# hh2019_proto_rev1_0_0.net
KiCad netlist of a schematic drawn in EAGLE
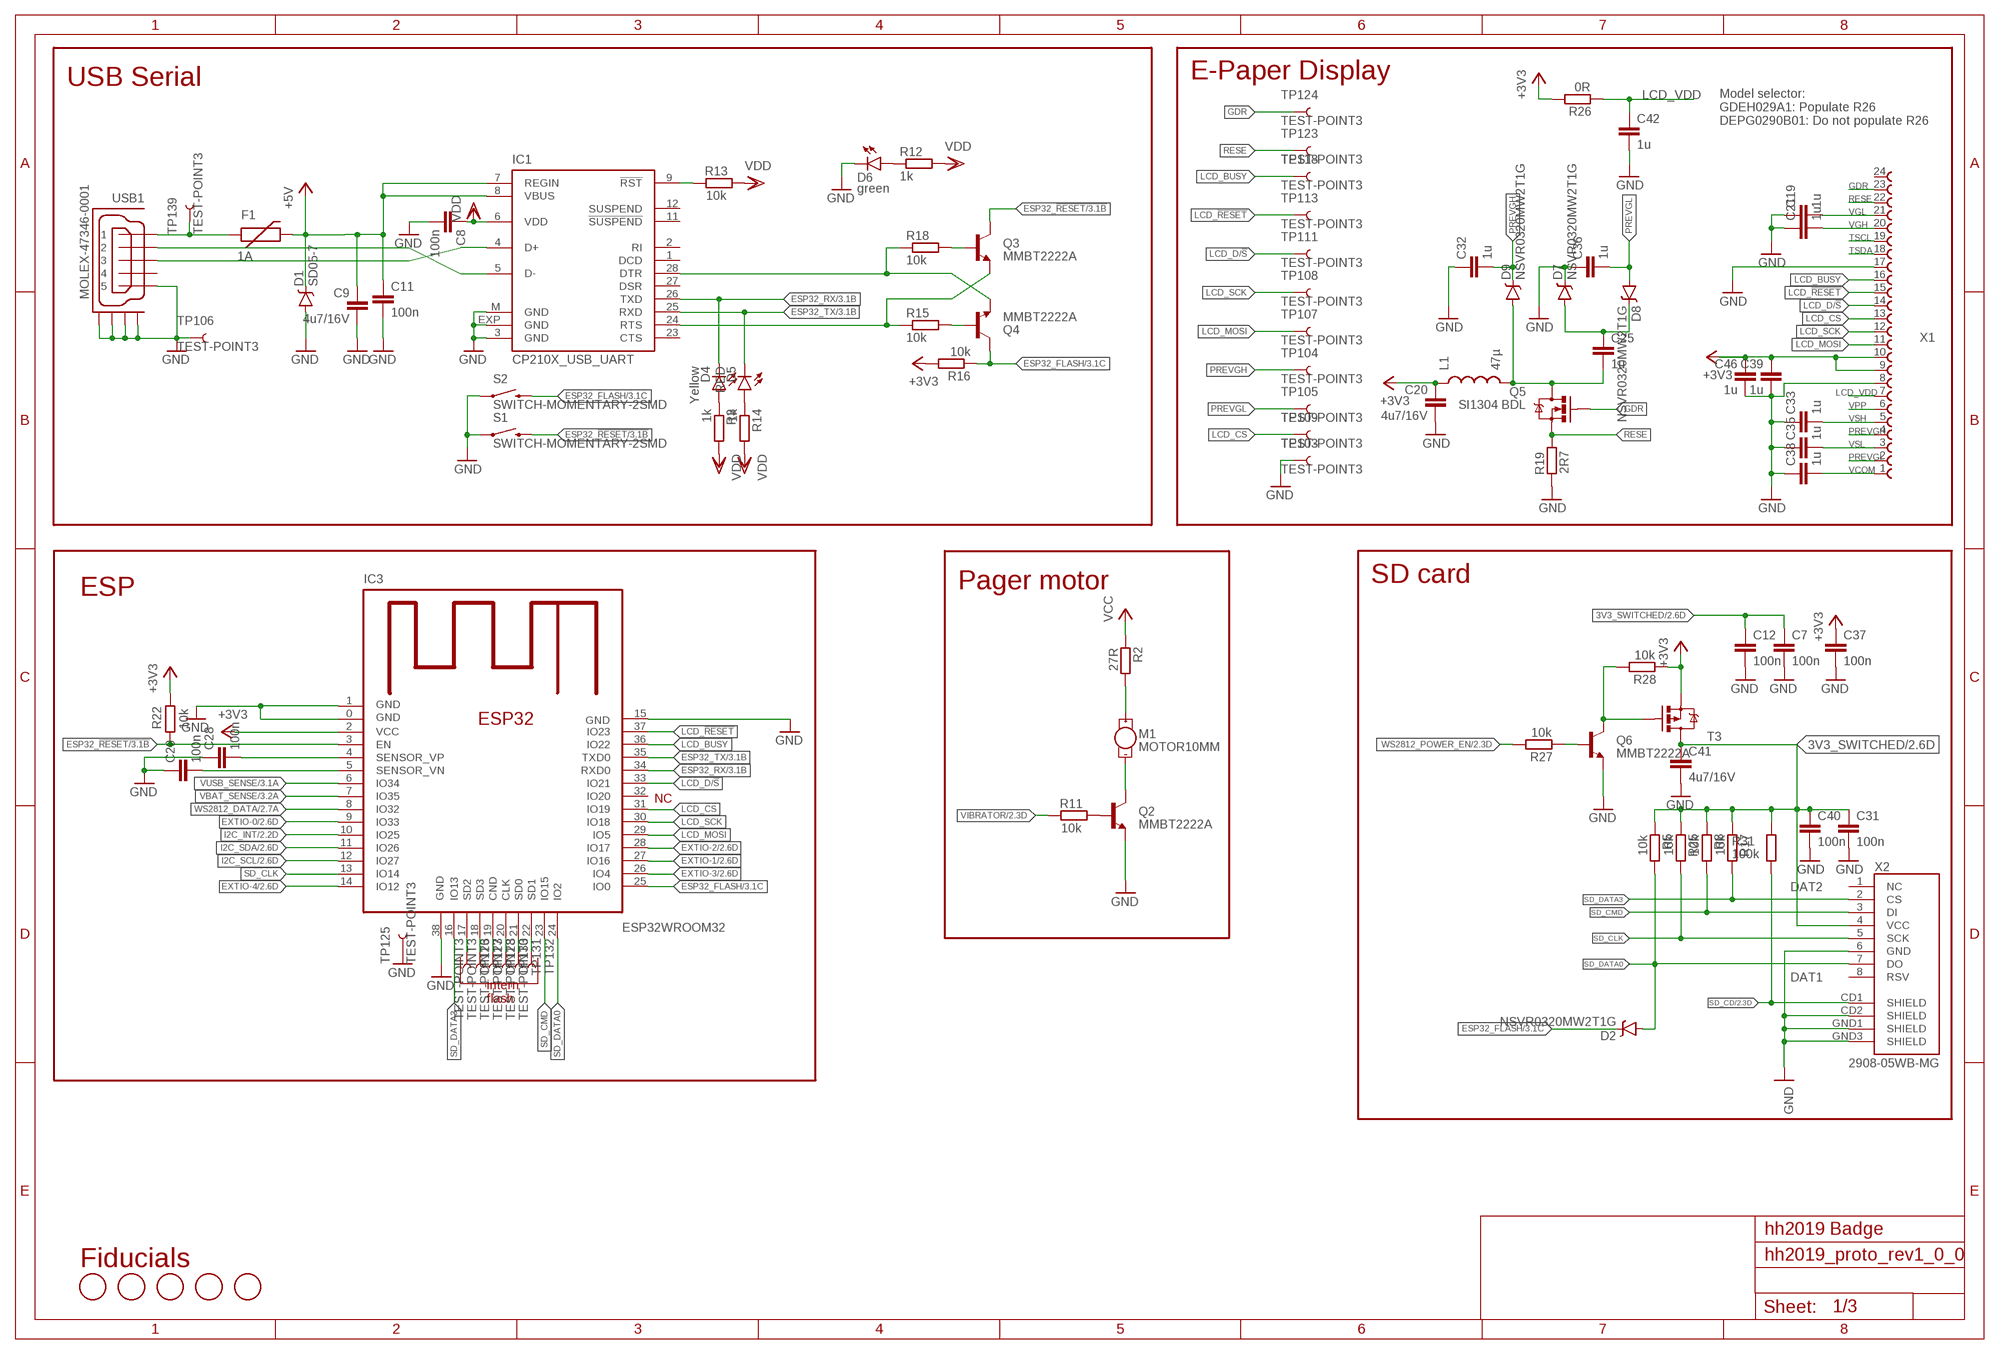
[diagram p0: schematic, sheet 1]
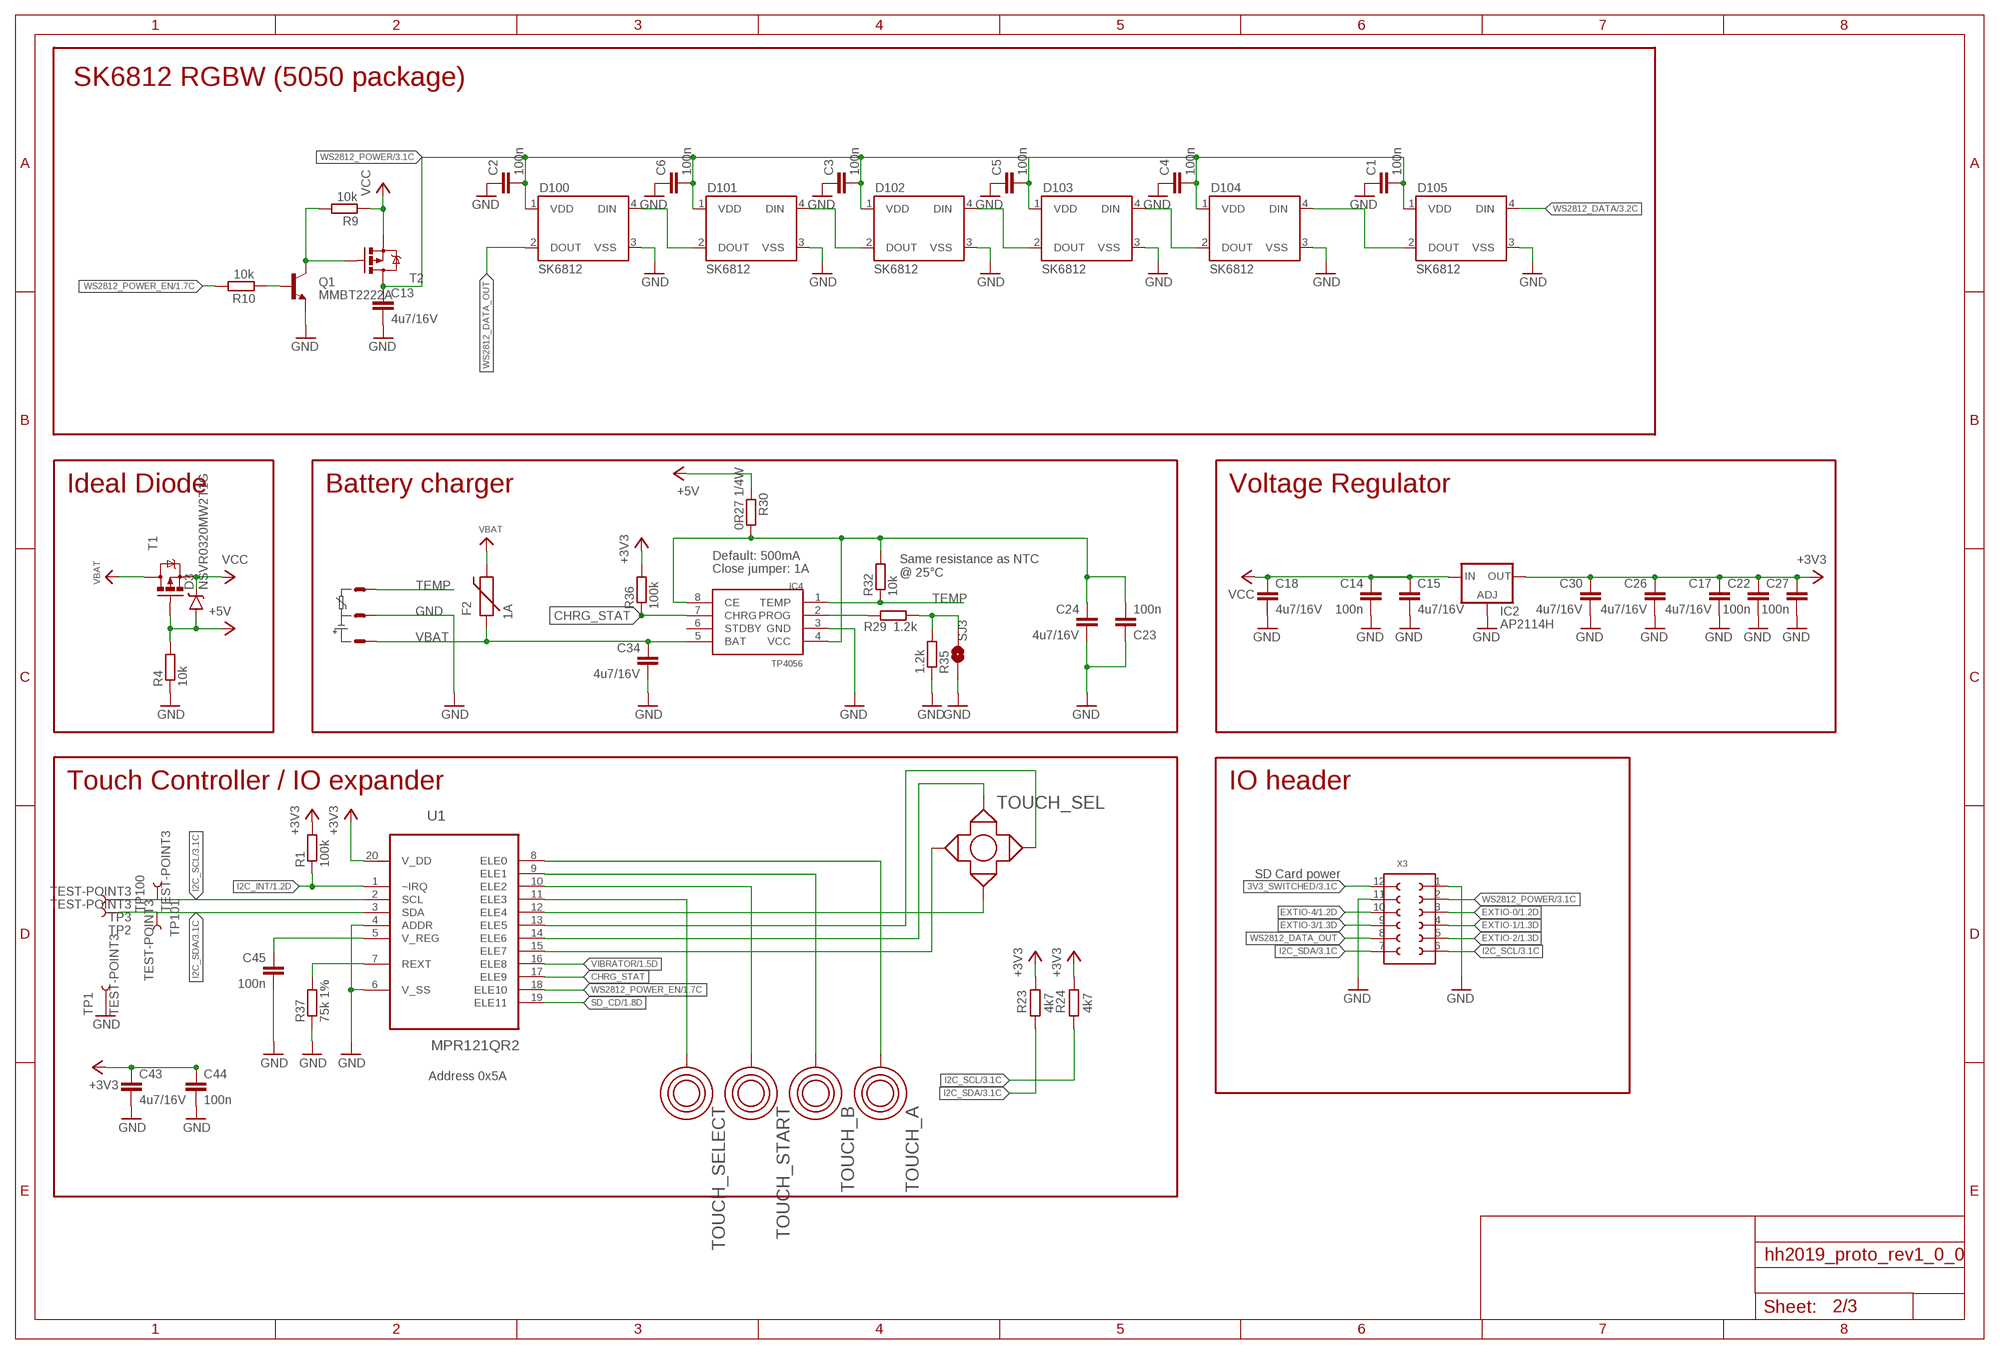
[diagram p1: schematic, sheet 2]
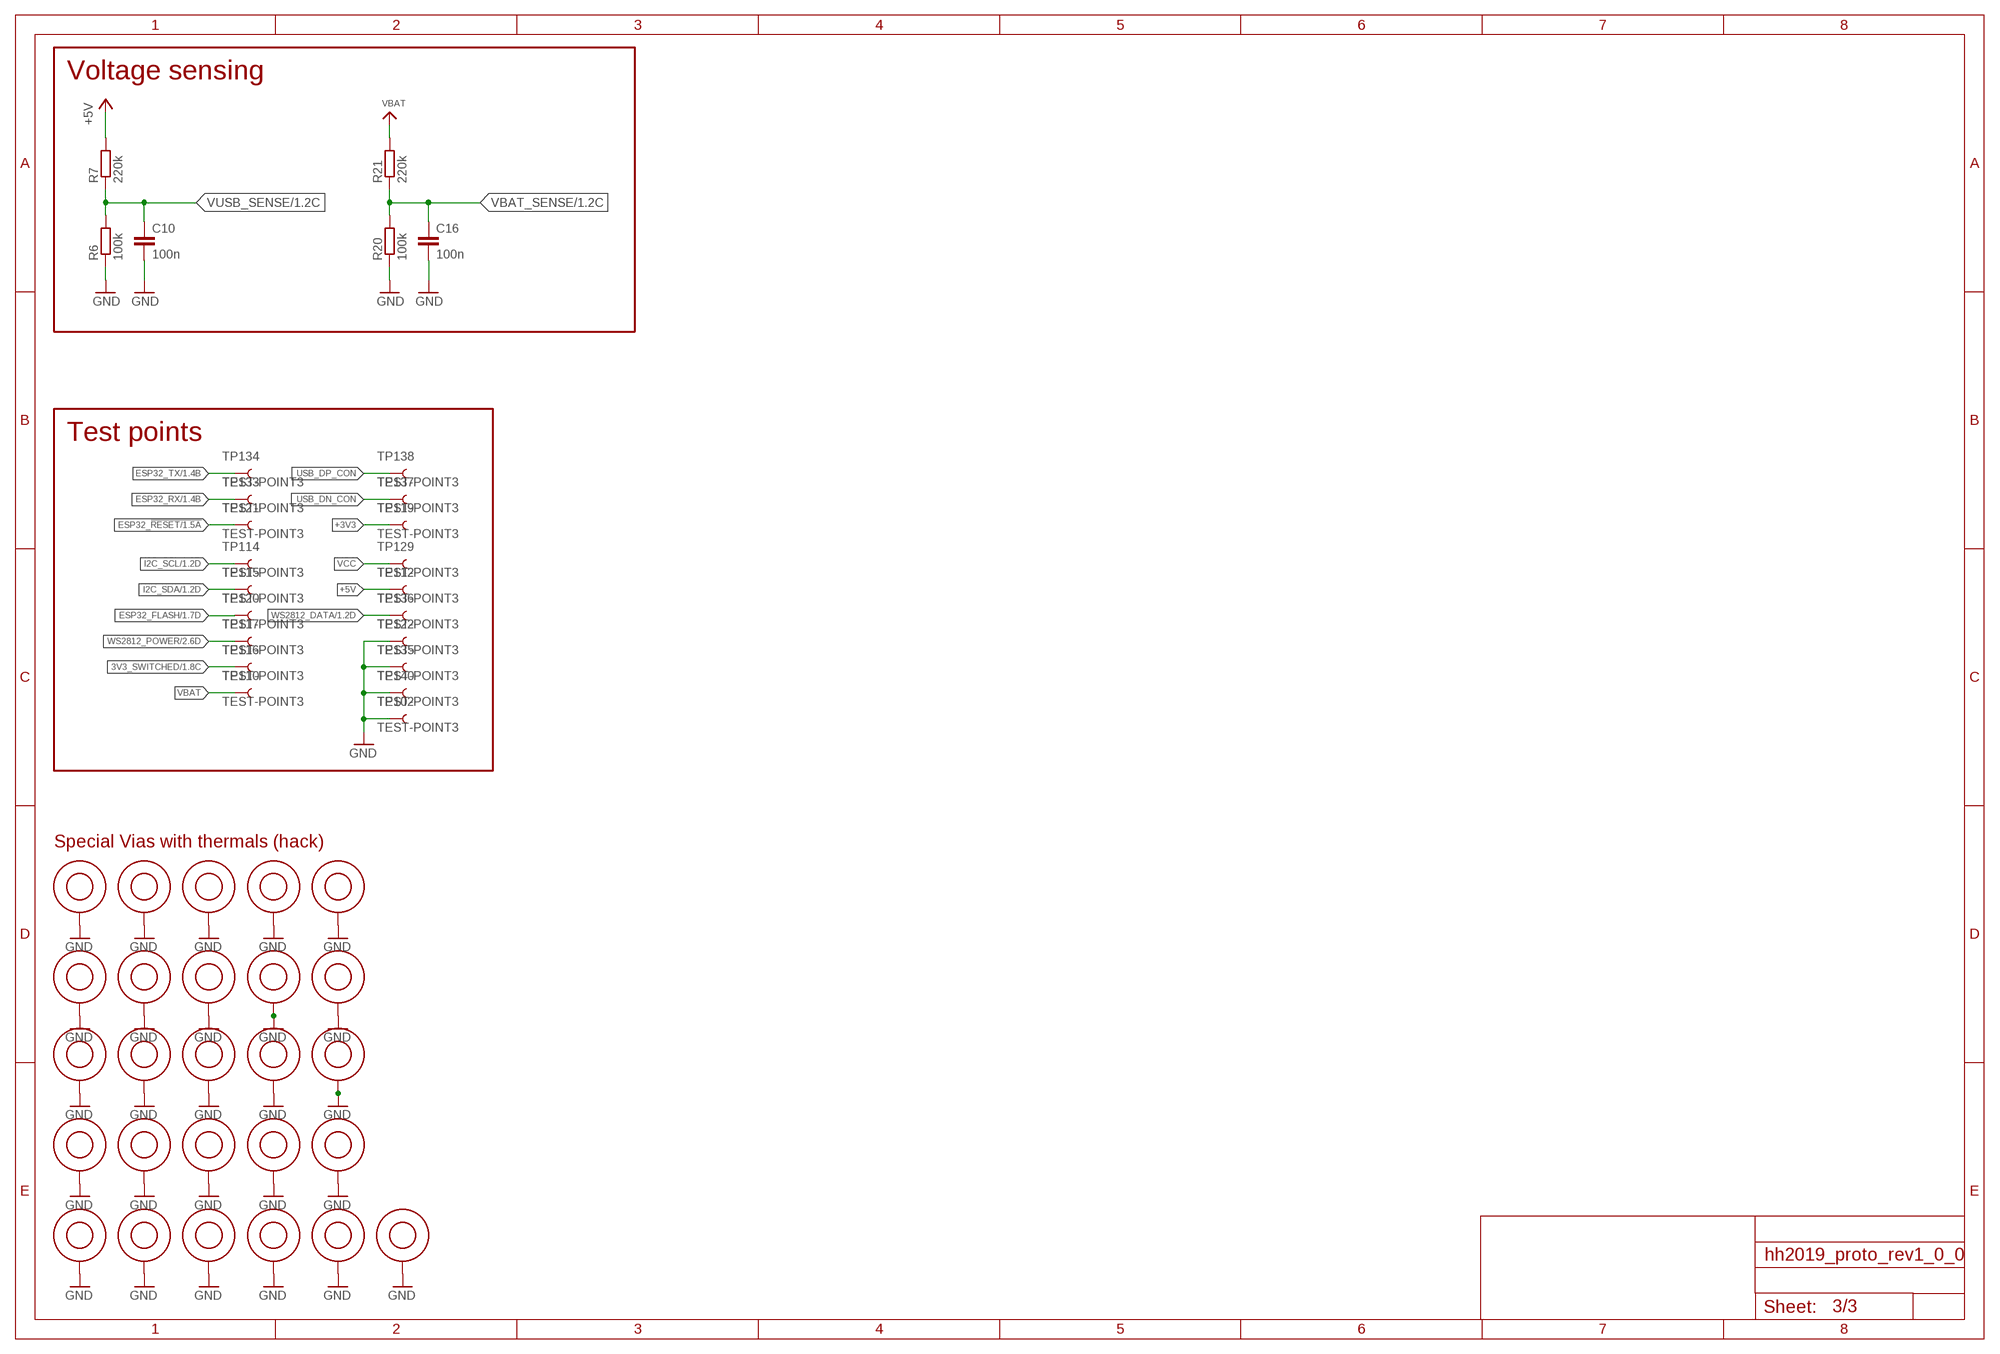
[diagram p2: schematic, sheet 3]

(export (version "E")
  (design (tool "Eeschema 10.0.6"))
  (components
    (comp (ref "C7")
      (value "100n")
      (footprint "eagle-import:C0603-DASHES")
      (fields (field (name "PARTNO") "GRM188R71H104KA93D"))
      (libsource (lib "eagle-import") (part "C0603-DASHES"))
    )
    (comp (ref "C8")
      (value "100n")
      (footprint "eagle-import:C0603-DASHES")
      (fields (field (name "PARTNO") "GRM188R71H104KA93D"))
      (libsource (lib "eagle-import") (part "C0603-DASHES"))
    )
    (comp (ref "C9")
      (value "4u7/16V")
      (footprint "eagle-import:C0805")
      (fields (field (name "PARTNO") "GRM21BR61C475KA88K"))
      (libsource (lib "eagle-import") (part "C-EUC0805"))
    )
    (comp (ref "C11")
      (value "100n")
      (footprint "eagle-import:C0603-DASHES")
      (fields (field (name "PARTNO") "GRM188R71H104KA93D"))
      (libsource (lib "eagle-import") (part "C0603-DASHES"))
    )
    (comp (ref "C12")
      (value "100n")
      (footprint "eagle-import:C0603-DASHES")
      (fields (field (name "PARTNO") "GRM188R71H104KA93D"))
      (libsource (lib "eagle-import") (part "C0603-DASHES"))
    )
    (comp (ref "C19")
      (value "1u")
      (footprint "eagle-import:C0603-DASHES")
      (fields (field (name "PARTNO") "GRM188R61E105KA12D"))
      (libsource (lib "eagle-import") (part "C0603-DASHES"))
    )
    (comp (ref "C20")
      (value "4u7/16V")
      (footprint "eagle-import:C0805")
      (fields (field (name "PARTNO") "GRM21BR61C475KA88K"))
      (libsource (lib "eagle-import") (part "C-EUC0805"))
    )
    (comp (ref "C21")
      (value "1u")
      (footprint "eagle-import:C0603-DASHES")
      (fields (field (name "PARTNO") "GRM188R61E105KA12D"))
      (libsource (lib "eagle-import") (part "C0603-DASHES"))
    )
    (comp (ref "C25")
      (value "1u")
      (footprint "eagle-import:C0603-DASHES")
      (fields (field (name "PARTNO") "GRM188R61E105KA12D"))
      (libsource (lib "eagle-import") (part "C0603-DASHES"))
    )
    (comp (ref "C28")
      (value "100n")
      (footprint "eagle-import:C0603-DASHES")
      (fields (field (name "PARTNO") "GRM188R71H104KA93D"))
      (libsource (lib "eagle-import") (part "C0603-DASHES"))
    )
    (comp (ref "C29")
      (value "100n")
      (footprint "eagle-import:C0603-DASHES")
      (fields (field (name "PARTNO") "GRM188R71H104KA93D"))
      (libsource (lib "eagle-import") (part "C0603-DASHES"))
    )
    (comp (ref "C31")
      (value "100n")
      (footprint "eagle-import:C0603-DASHES")
      (fields (field (name "PARTNO") "GRM188R71H104KA93D"))
      (libsource (lib "eagle-import") (part "C0603-DASHES"))
    )
    (comp (ref "C32")
      (value "1u")
      (footprint "eagle-import:C0603-DASHES")
      (fields (field (name "PARTNO") "GRM188R61E105KA12D"))
      (libsource (lib "eagle-import") (part "C0603-DASHES"))
    )
    (comp (ref "C33")
      (value "1u")
      (footprint "eagle-import:C0603-DASHES")
      (fields (field (name "PARTNO") "GRM188R61E105KA12D"))
      (libsource (lib "eagle-import") (part "C0603-DASHES"))
    )
    (comp (ref "C35")
      (value "1u")
      (footprint "eagle-import:C0603-DASHES")
      (fields (field (name "PARTNO") "GRM188R61E105KA12D"))
      (libsource (lib "eagle-import") (part "C0603-DASHES"))
    )
    (comp (ref "C36")
      (value "1u")
      (footprint "eagle-import:C0603-DASHES")
      (fields (field (name "PARTNO") "GRM188R61E105KA12D"))
      (libsource (lib "eagle-import") (part "C0603-DASHES"))
    )
    (comp (ref "C37")
      (value "100n")
      (footprint "eagle-import:C0603-DASHES")
      (fields (field (name "PARTNO") "GRM188R71H104KA93D"))
      (libsource (lib "eagle-import") (part "C0603-DASHES"))
    )
    (comp (ref "C38")
      (value "1u")
      (footprint "eagle-import:C0603-DASHES")
      (fields (field (name "PARTNO") "GRM188R61E105KA12D"))
      (libsource (lib "eagle-import") (part "C0603-DASHES"))
    )
    (comp (ref "C39")
      (value "1u")
      (footprint "eagle-import:C0603-DASHES")
      (fields (field (name "PARTNO") "GRM188R61E105KA12D"))
      (libsource (lib "eagle-import") (part "C0603-DASHES"))
    )
    (comp (ref "C40")
      (value "100n")
      (footprint "eagle-import:C0603-DASHES")
      (fields (field (name "PARTNO") "GRM188R71H104KA93D"))
      (libsource (lib "eagle-import") (part "C0603-DASHES"))
    )
    (comp (ref "C41")
      (value "4u7/16V")
      (footprint "eagle-import:C0805")
      (fields (field (name "PARTNO") "GRM21BR61C475KA88K"))
      (libsource (lib "eagle-import") (part "C-EUC0805"))
    )
    (comp (ref "C42")
      (value "1u")
      (footprint "eagle-import:C0603-DASHES")
      (fields (field (name "PARTNO") "GRM188R61E105KA12D"))
      (libsource (lib "eagle-import") (part "C0603-DASHES"))
    )
    (comp (ref "C46")
      (value "1u")
      (footprint "eagle-import:C0603-DASHES")
      (fields (field (name "PARTNO") "GRM188R61E105KA12D"))
      (libsource (lib "eagle-import") (part "C0603-DASHES"))
    )
    (comp (ref "D1")
      (value "SD05-7")
      (footprint "eagle-import:SOD-323")
      (libsource (lib "eagle-import") (part "DIODE-SCHOTTKY-PMEG4005EJ"))
    )
    (comp (ref "D2")
      (value "NSVR0320MW2T1G")
      (footprint "eagle-import:SOD-323")
      (fields (field (name "PARTNO") "BAT20JFILM"))
      (libsource (lib "eagle-import") (part "BAT20JFILM"))
    )
    (comp (ref "D4")
      (value "Yellow")
      (footprint "eagle-import:LED-0603")
      (libsource (lib "eagle-import") (part "LED0603"))
    )
    (comp (ref "D5")
      (value "RED")
      (footprint "eagle-import:LED-0603")
      (libsource (lib "eagle-import") (part "LED0603"))
    )
    (comp (ref "D6")
      (value "green")
      (footprint "eagle-import:LED-0603")
      (libsource (lib "eagle-import") (part "LED0603"))
    )
    (comp (ref "D7")
      (value "NSVR0320MW2T1G")
      (footprint "eagle-import:SOD-323")
      (fields (field (name "PARTNO") "BAT20JFILM"))
      (libsource (lib "eagle-import") (part "BAT20JFILM"))
    )
    (comp (ref "D8")
      (value "NSVR0320MW2T1G")
      (footprint "eagle-import:SOD-323")
      (fields (field (name "PARTNO") "BAT20JFILM"))
      (libsource (lib "eagle-import") (part "BAT20JFILM"))
    )
    (comp (ref "D9")
      (value "NSVR0320MW2T1G")
      (footprint "eagle-import:SOD-323")
      (fields (field (name "PARTNO") "BAT20JFILM"))
      (libsource (lib "eagle-import") (part "BAT20JFILM"))
    )
    (comp (ref "F1")
      (value "1A")
      (footprint "eagle-import:PTC-1206")
      (libsource (lib "eagle-import") (part "PTCSMD"))
    )
    (comp (ref "FD1")
      (value "FIDUCIAL")
      (footprint "eagle-import:FIDUCIAL_1MM")
      (fields (field (name "PARTNO") "NAP"))
      (libsource (lib "eagle-import") (part "FIDUCIAL"))
    )
    (comp (ref "FD2")
      (value "FIDUCIAL")
      (footprint "eagle-import:FIDUCIAL_1MM")
      (fields (field (name "PARTNO") "NAP"))
      (libsource (lib "eagle-import") (part "FIDUCIAL"))
    )
    (comp (ref "FD3")
      (value "FIDUCIAL")
      (footprint "eagle-import:FIDUCIAL_1MM")
      (fields (field (name "PARTNO") "NAP"))
      (libsource (lib "eagle-import") (part "FIDUCIAL"))
    )
    (comp (ref "FD4")
      (value "FIDUCIAL")
      (footprint "eagle-import:FIDUCIAL_1MM")
      (fields (field (name "PARTNO") "NAP"))
      (libsource (lib "eagle-import") (part "FIDUCIAL"))
    )
    (comp (ref "FD5")
      (value "FIDUCIAL")
      (footprint "eagle-import:FIDUCIAL_1MM")
      (fields (field (name "PARTNO") "NAP"))
      (libsource (lib "eagle-import") (part "FIDUCIAL"))
    )
    (comp (ref "IC1")
      (value "CP210X_USB_UART")
      (footprint "eagle-import:MLP28")
      (fields (field (name "PARTNO") "CP2102-GMR"))
      (libsource (lib "eagle-import") (part "CP210X_USB_UART"))
    )
    (comp (ref "IC3")
      (value "ESP32WROOM32")
      (footprint "eagle-import:ESP32MOD")
      (libsource (lib "eagle-import") (part "ESP32WROOM32"))
    )
    (comp (ref "L1")
      (value "47µ")
      (footprint "eagle-import:1210")
      (fields (field (name "PARTNO") "NLCV32T-220K-EF"))
      (libsource (lib "eagle-import") (part "INDUCTOR1210"))
    )
    (comp (ref "M1")
      (value "MOTOR10MM")
      (footprint "eagle-import:VIBE-MOTOR-10MM")
      (libsource (lib "eagle-import") (part "MOTOR10MM"))
    )
    (comp (ref "Q2")
      (value "MMBT2222A")
      (footprint "eagle-import:SOT23-3")
      (fields (field (name "PARTNO") "BC817-25,215"))
      (libsource (lib "eagle-import") (part "TRANSISTOR_NPNMMBT2222A"))
    )
    (comp (ref "Q3")
      (value "MMBT2222A")
      (footprint "eagle-import:SOT23-3")
      (fields (field (name "PARTNO") "BC817-25,215"))
      (libsource (lib "eagle-import") (part "TRANSISTOR_NPNMMBT2222A"))
    )
    (comp (ref "Q4")
      (value "MMBT2222A")
      (footprint "eagle-import:SOT23-3")
      (fields (field (name "PARTNO") "BC817-25,215"))
      (libsource (lib "eagle-import") (part "TRANSISTOR_NPNMMBT2222A"))
    )
    (comp (ref "Q5")
      (value "SI1304 BDL")
      (footprint "eagle-import:SOT323")
      (fields (field (name "PARTNO") "SI1308EDL-T1-GE3"))
      (libsource (lib "eagle-import") (part "MOSFET-NCHANNEL2N7002PW"))
    )
    (comp (ref "Q6")
      (value "MMBT2222A")
      (footprint "eagle-import:SOT23-3")
      (fields (field (name "PARTNO") "BC817-25,215"))
      (libsource (lib "eagle-import") (part "TRANSISTOR_NPNMMBT2222A"))
    )
    (comp (ref "R2")
      (value "27R")
      (footprint "eagle-import:R1206")
      (fields (field (name "PARTNO") "ERJ-3GEYJ220V"))
      (libsource (lib "eagle-import") (part "R-EU_R1206"))
    )
    (comp (ref "R3")
      (value "1k")
      (footprint "eagle-import:R0603-DASHES")
      (fields (field (name "PARTNO") "ERJ-3GEYJ102V"))
      (libsource (lib "eagle-import") (part "hh2019_rev0_1_0_dev_R0603-DASHES"))
    )
    (comp (ref "R5")
      (value "10k")
      (footprint "eagle-import:R0603-DASHES")
      (fields (field (name "PARTNO") "ERJ-3GEYJ103V"))
      (libsource (lib "eagle-import") (part "R0603-DASHES"))
    )
    (comp (ref "R8")
      (value "10k")
      (footprint "eagle-import:R0603-DASHES")
      (fields (field (name "PARTNO") "ERJ-3GEYJ103V"))
      (libsource (lib "eagle-import") (part "R0603-DASHES"))
    )
    (comp (ref "R11")
      (value "10k")
      (footprint "eagle-import:R0603-DASHES")
      (fields (field (name "PARTNO") "ERJ-3GEYJ103V"))
      (libsource (lib "eagle-import") (part "R0603-DASHES"))
    )
    (comp (ref "R12")
      (value "1k")
      (footprint "eagle-import:R0603-DASHES")
      (fields (field (name "PARTNO") "ERJ-3GEYJ102V"))
      (libsource (lib "eagle-import") (part "hh2019_rev0_1_0_dev_R0603-DASHES"))
    )
    (comp (ref "R13")
      (value "10k")
      (footprint "eagle-import:R0603-DASHES")
      (fields (field (name "PARTNO") "ERJ-3GEYJ103V"))
      (libsource (lib "eagle-import") (part "hh2019_rev0_1_0_dev_R0603-DASHES"))
    )
    (comp (ref "R14")
      (value "1k")
      (footprint "eagle-import:R0603-DASHES")
      (fields (field (name "PARTNO") "ERJ-3GEYJ102V"))
      (libsource (lib "eagle-import") (part "hh2019_rev0_1_0_dev_R0603-DASHES"))
    )
    (comp (ref "R15")
      (value "10k")
      (footprint "eagle-import:R0603-DASHES")
      (fields (field (name "PARTNO") "ERJ-3GEYJ103V"))
      (libsource (lib "eagle-import") (part "hh2019_rev0_1_0_dev_R0603-DASHES"))
    )
    (comp (ref "R16")
      (value "10k")
      (footprint "eagle-import:R0603-DASHES")
      (fields (field (name "PARTNO") "ERJ-3GEYJ103V"))
      (libsource (lib "eagle-import") (part "hh2019_rev0_1_0_dev_R0603-DASHES"))
    )
    (comp (ref "R17")
      (value "10k")
      (footprint "eagle-import:R0603-DASHES")
      (fields (field (name "PARTNO") "ERJ-3GEYJ103V"))
      (libsource (lib "eagle-import") (part "hh2019_rev0_1_0_dev_R0603-DASHES"))
    )
    (comp (ref "R18")
      (value "10k")
      (footprint "eagle-import:R0603-DASHES")
      (fields (field (name "PARTNO") "ERJ-3GEYJ103V"))
      (libsource (lib "eagle-import") (part "hh2019_rev0_1_0_dev_R0603-DASHES"))
    )
    (comp (ref "R19")
      (value "2R7")
      (footprint "eagle-import:R0603-DASHES")
      (fields (field (name "PARTNO") "ERJ-3GEYJ5R1V"))
      (libsource (lib "eagle-import") (part "hh2019_rev0_1_0_dev_R0603-DASHES"))
    )
    (comp (ref "R22")
      (value "10k")
      (footprint "eagle-import:R0603-DASHES")
      (fields (field (name "PARTNO") "ERJ-3GEYJ103V"))
      (libsource (lib "eagle-import") (part "hh2019_rev0_1_0_dev_R0603-DASHES"))
    )
    (comp (ref "R25")
      (value "10k")
      (footprint "eagle-import:R0603-DASHES")
      (fields (field (name "PARTNO") "ERJ-3GEYJ103V"))
      (libsource (lib "eagle-import") (part "hh2019_rev0_1_0_dev_R0603-DASHES"))
    )
    (comp (ref "R26")
      (value "0R")
      (footprint "eagle-import:R0603-DASHES")
      (fields (field (name "PARTNO") "ERJ-3GEYJ5R1V"))
      (libsource (lib "eagle-import") (part "hh2019_rev0_1_0_dev_R0603-DASHES"))
    )
    (comp (ref "R27")
      (value "10k")
      (footprint "eagle-import:R0603-DASHES")
      (fields (field (name "PARTNO") "ERJ-3GEYJ103V"))
      (libsource (lib "eagle-import") (part "R0603-DASHES"))
    )
    (comp (ref "R28")
      (value "10k")
      (footprint "eagle-import:R0603-DASHES")
      (fields (field (name "PARTNO") "ERJ-3GEYJ103V"))
      (libsource (lib "eagle-import") (part "R0603-DASHES"))
    )
    (comp (ref "R31")
      (value "100k")
      (footprint "eagle-import:R0603-DASHES")
      (fields (field (name "PARTNO") "ERJ-3GEYJ104V"))
      (libsource (lib "eagle-import") (part "hh2019_rev0_1_0_dev_R0603-DASHES"))
    )
    (comp (ref "S1")
      (value "SWITCH-MOMENTARY-2SMD")
      (footprint "eagle-import:TACTILE-SWITCH-SMD")
      (fields (field (name "PARTNO") "SKQGABE010"))
      (libsource (lib "eagle-import") (part "SWITCH-MOMENTARY-2SMD"))
    )
    (comp (ref "S2")
      (value "SWITCH-MOMENTARY-2SMD")
      (footprint "eagle-import:TACTILE-SWITCH-SMD")
      (fields (field (name "PARTNO") "SKQGABE010"))
      (libsource (lib "eagle-import") (part "SWITCH-MOMENTARY-2SMD"))
    )
    (comp (ref "T3")
      (value "MOSFET-PCHANNEL")
      (footprint "eagle-import:SOT23-3")
      (libsource (lib "eagle-import") (part "MOSFET-PCHANNEL"))
    )
    (comp (ref "TP103")
      (value "TEST-POINT3")
      (footprint "eagle-import:PAD.03X.03")
      (fields (field (name "PARTNO") "NAP"))
      (libsource (lib "eagle-import") (part "TEST-POINT3"))
    )
    (comp (ref "TP104")
      (value "TEST-POINT3")
      (footprint "eagle-import:PAD.03X.03")
      (fields (field (name "PARTNO") "NAP"))
      (libsource (lib "eagle-import") (part "TEST-POINT3"))
    )
    (comp (ref "TP105")
      (value "TEST-POINT3")
      (footprint "eagle-import:PAD.03X.03")
      (fields (field (name "PARTNO") "NAP"))
      (libsource (lib "eagle-import") (part "TEST-POINT3"))
    )
    (comp (ref "TP106")
      (value "TEST-POINT3")
      (footprint "eagle-import:PAD.03X.03")
      (fields (field (name "PARTNO") "NAP"))
      (libsource (lib "eagle-import") (part "TEST-POINT3"))
    )
    (comp (ref "TP107")
      (value "TEST-POINT3")
      (footprint "eagle-import:PAD.03X.03")
      (fields (field (name "PARTNO") "NAP"))
      (libsource (lib "eagle-import") (part "TEST-POINT3"))
    )
    (comp (ref "TP108")
      (value "TEST-POINT3")
      (footprint "eagle-import:PAD.03X.03")
      (fields (field (name "PARTNO") "NAP"))
      (libsource (lib "eagle-import") (part "TEST-POINT3"))
    )
    (comp (ref "TP109")
      (value "TEST-POINT3")
      (footprint "eagle-import:PAD.03X.03")
      (fields (field (name "PARTNO") "NAP"))
      (libsource (lib "eagle-import") (part "TEST-POINT3"))
    )
    (comp (ref "TP111")
      (value "TEST-POINT3")
      (footprint "eagle-import:PAD.03X.03")
      (fields (field (name "PARTNO") "NAP"))
      (libsource (lib "eagle-import") (part "TEST-POINT3"))
    )
    (comp (ref "TP113")
      (value "TEST-POINT3")
      (footprint "eagle-import:PAD.03X.03")
      (fields (field (name "PARTNO") "NAP"))
      (libsource (lib "eagle-import") (part "TEST-POINT3"))
    )
    (comp (ref "TP118")
      (value "TEST-POINT3")
      (footprint "eagle-import:PAD.03X.03")
      (fields (field (name "PARTNO") "NAP"))
      (libsource (lib "eagle-import") (part "TEST-POINT3"))
    )
    (comp (ref "TP123")
      (value "TEST-POINT3")
      (footprint "eagle-import:PAD.03X.03")
      (fields (field (name "PARTNO") "NAP"))
      (libsource (lib "eagle-import") (part "TEST-POINT3"))
    )
    (comp (ref "TP124")
      (value "TEST-POINT3")
      (footprint "eagle-import:PAD.03X.03")
      (fields (field (name "PARTNO") "NAP"))
      (libsource (lib "eagle-import") (part "TEST-POINT3"))
    )
    (comp (ref "TP125")
      (value "TEST-POINT3")
      (footprint "eagle-import:PAD.03X.03")
      (fields (field (name "PARTNO") "NAP"))
      (libsource (lib "eagle-import") (part "TEST-POINT3"))
    )
    (comp (ref "TP126")
      (value "TEST-POINT3")
      (footprint "eagle-import:PAD.03X.03")
      (fields (field (name "PARTNO") "NAP"))
      (libsource (lib "eagle-import") (part "TEST-POINT3"))
    )
    (comp (ref "TP127")
      (value "TEST-POINT3")
      (footprint "eagle-import:PAD.03X.03")
      (fields (field (name "PARTNO") "NAP"))
      (libsource (lib "eagle-import") (part "TEST-POINT3"))
    )
    (comp (ref "TP128")
      (value "TEST-POINT3")
      (footprint "eagle-import:PAD.03X.03")
      (fields (field (name "PARTNO") "NAP"))
      (libsource (lib "eagle-import") (part "TEST-POINT3"))
    )
    (comp (ref "TP130")
      (value "TEST-POINT3")
      (footprint "eagle-import:PAD.03X.03")
      (fields (field (name "PARTNO") "NAP"))
      (libsource (lib "eagle-import") (part "TEST-POINT3"))
    )
    (comp (ref "TP131")
      (value "TEST-POINT3")
      (footprint "eagle-import:PAD.03X.03")
      (fields (field (name "PARTNO") "NAP"))
      (libsource (lib "eagle-import") (part "TEST-POINT3"))
    )
    (comp (ref "TP132")
      (value "TEST-POINT3")
      (footprint "eagle-import:PAD.03X.03")
      (fields (field (name "PARTNO") "NAP"))
      (libsource (lib "eagle-import") (part "TEST-POINT3"))
    )
    (comp (ref "TP139")
      (value "TEST-POINT3")
      (footprint "eagle-import:PAD.03X.03")
      (fields (field (name "PARTNO") "NAP"))
      (libsource (lib "eagle-import") (part "TEST-POINT3"))
    )
    (comp (ref "USB1")
      (value "MOLEX-47346-0001")
      (footprint "eagle-import:MOLEX-47364-0001")
      (fields (field (name "PARTNO") "10118192-0001LF"))
      (libsource (lib "eagle-import") (part "MOLEX-47346-0001"))
    )
    (comp (ref "X1")
      (value "68712414022")
      (footprint "eagle-import:68712414022")
      (libsource (lib "eagle-import") (part "68712414022"))
    )
    (comp (ref "X2")
      (value "2908-05WB-MG")
      (footprint "eagle-import:MICRO-SD-SOCKET-PP")
      (libsource (lib "eagle-import") (part "2908-05WB-MG"))
    )
    (comp (ref "C1")
      (value "100n")
      (footprint "eagle-import:C0603-DASHES")
      (fields (field (name "PARTNO") "GRM188R71H104KA93D"))
      (libsource (lib "eagle-import") (part "C0603-DASHES"))
    )
    (comp (ref "C2")
      (value "100n")
      (footprint "eagle-import:C0603-DASHES")
      (fields (field (name "PARTNO") "GRM188R71H104KA93D"))
      (libsource (lib "eagle-import") (part "C0603-DASHES"))
    )
    (comp (ref "C3")
      (value "100n")
      (footprint "eagle-import:C0603-DASHES")
      (fields (field (name "PARTNO") "GRM188R71H104KA93D"))
      (libsource (lib "eagle-import") (part "C0603-DASHES"))
    )
    (comp (ref "C4")
      (value "100n")
      (footprint "eagle-import:C0603-DASHES")
      (fields (field (name "PARTNO") "GRM188R71H104KA93D"))
      (libsource (lib "eagle-import") (part "C0603-DASHES"))
    )
    (comp (ref "C5")
      (value "100n")
      (footprint "eagle-import:C0603-DASHES")
      (fields (field (name "PARTNO") "GRM188R71H104KA93D"))
      (libsource (lib "eagle-import") (part "C0603-DASHES"))
    )
    (comp (ref "C6")
      (value "100n")
      (footprint "eagle-import:C0603-DASHES")
      (fields (field (name "PARTNO") "GRM188R71H104KA93D"))
      (libsource (lib "eagle-import") (part "C0603-DASHES"))
    )
    (comp (ref "C13")
      (value "4u7/16V")
      (footprint "eagle-import:C0805")
      (fields (field (name "PARTNO") "GRM21BR61C475KA88K"))
      (libsource (lib "eagle-import") (part "C-EUC0805"))
    )
    (comp (ref "C14")
      (value "100n")
      (footprint "eagle-import:C0603-DASHES")
      (fields (field (name "PARTNO") "GRM188R71H104KA93D"))
      (libsource (lib "eagle-import") (part "C0603-DASHES"))
    )
    (comp (ref "C15")
      (value "4u7/16V")
      (footprint "eagle-import:C0805")
      (fields (field (name "PARTNO") "GRM21BR61C475KA88K"))
      (libsource (lib "eagle-import") (part "C-EUC0805"))
    )
    (comp (ref "C17")
      (value "4u7/16V")
      (footprint "eagle-import:C0805")
      (fields (field (name "PARTNO") "GRM21BR61C475KA88K"))
      (libsource (lib "eagle-import") (part "C-EUC0805"))
    )
    (comp (ref "C18")
      (value "4u7/16V")
      (footprint "eagle-import:C0805")
      (fields (field (name "PARTNO") "GRM21BR61C475KA88K"))
      (libsource (lib "eagle-import") (part "C-EUC0805"))
    )
    (comp (ref "C22")
      (value "100n")
      (footprint "eagle-import:C0603-DASHES")
      (fields (field (name "PARTNO") "GRM188R71H104KA93D"))
      (libsource (lib "eagle-import") (part "C0603-DASHES"))
    )
    (comp (ref "C23")
      (value "100n")
      (footprint "eagle-import:C0603-DASHES")
      (fields (field (name "PARTNO") "GRM188R71H104KA93D"))
      (libsource (lib "eagle-import") (part "C0603-DASHES"))
    )
    (comp (ref "C24")
      (value "4u7/16V")
      (footprint "eagle-import:C0805")
      (fields (field (name "PARTNO") "GRM21BR61C475KA88K"))
      (libsource (lib "eagle-import") (part "C-EUC0805"))
    )
    (comp (ref "C26")
      (value "4u7/16V")
      (footprint "eagle-import:C0805")
      (fields (field (name "PARTNO") "GRM21BR61C475KA88K"))
      (libsource (lib "eagle-import") (part "C-EUC0805"))
    )
    (comp (ref "C27")
      (value "100n")
      (footprint "eagle-import:C0603-DASHES")
      (fields (field (name "PARTNO") "GRM188R71H104KA93D"))
      (libsource (lib "eagle-import") (part "C0603-DASHES"))
    )
    (comp (ref "C30")
      (value "4u7/16V")
      (footprint "eagle-import:C0805")
      (fields (field (name "PARTNO") "GRM21BR61C475KA88K"))
      (libsource (lib "eagle-import") (part "C-EUC0805"))
    )
    (comp (ref "C34")
      (value "4u7/16V")
      (footprint "eagle-import:C0805")
      (fields (field (name "PARTNO") "GRM21BR61C475KA88K"))
      (libsource (lib "eagle-import") (part "C-EUC0805"))
    )
    (comp (ref "C43")
      (value "4u7/16V")
      (footprint "eagle-import:C0805")
      (fields (field (name "PARTNO") "GRM21BR61C475KA88K"))
      (libsource (lib "eagle-import") (part "C-EUC0805"))
    )
    (comp (ref "C44")
      (value "100n")
      (footprint "eagle-import:C0603-DASHES")
      (fields (field (name "PARTNO") "GRM188R71H104KA93D"))
      (libsource (lib "eagle-import") (part "C0603-DASHES"))
    )
    (comp (ref "C45")
      (value "100n")
      (footprint "eagle-import:C0603-DASHES")
      (fields (field (name "PARTNO") "GRM188R71H104KA93D"))
      (libsource (lib "eagle-import") (part "C0603-DASHES"))
    )
    (comp (ref "D3")
      (value "NSVR0320MW2T1G")
      (footprint "eagle-import:SOD-323")
      (fields (field (name "PARTNO") "BAT20JFILM"))
      (libsource (lib "eagle-import") (part "BAT20JFILM"))
    )
    (comp (ref "D100")
      (value "SK6812")
      (footprint "eagle-import:WS2812B")
      (libsource (lib "eagle-import") (part "WS2812B"))
    )
    (comp (ref "D101")
      (value "SK6812")
      (footprint "eagle-import:WS2812B")
      (libsource (lib "eagle-import") (part "WS2812B"))
    )
    (comp (ref "D102")
      (value "SK6812")
      (footprint "eagle-import:WS2812B")
      (libsource (lib "eagle-import") (part "WS2812B"))
    )
    (comp (ref "D103")
      (value "SK6812")
      (footprint "eagle-import:WS2812B")
      (libsource (lib "eagle-import") (part "WS2812B"))
    )
    (comp (ref "D104")
      (value "SK6812")
      (footprint "eagle-import:WS2812B")
      (libsource (lib "eagle-import") (part "WS2812B"))
    )
    (comp (ref "D105")
      (value "SK6812")
      (footprint "eagle-import:WS2812B")
      (libsource (lib "eagle-import") (part "WS2812B"))
    )
    (comp (ref "F2")
      (value "1A")
      (footprint "eagle-import:PTC-1206")
      (libsource (lib "eagle-import") (part "PTCSMD"))
    )
    (comp (ref "IC2")
      (value "AP2114H")
      (footprint "eagle-import:SOT223")
      (fields (field (name "PARTNO") "AP7215-33YG-13"))
      (libsource (lib "eagle-import") (part "LD117A?S33TR"))
    )
    (comp (ref "IC4")
      (value "TP4056")
      (footprint "eagle-import:SOP-8")
      (libsource (lib "eagle-import") (part "TP4056"))
    )
    (comp (ref "Q1")
      (value "MMBT2222A")
      (footprint "eagle-import:SOT23-3")
      (fields (field (name "PARTNO") "BC817-25,215"))
      (libsource (lib "eagle-import") (part "TRANSISTOR_NPNMMBT2222A"))
    )
    (comp (ref "R1")
      (value "100k")
      (footprint "eagle-import:R0603-DASHES")
      (fields (field (name "PARTNO") "ERJ-3GEYJ104V"))
      (libsource (lib "eagle-import") (part "hh2019_rev0_1_0_dev_R0603-DASHES"))
    )
    (comp (ref "R4")
      (value "10k")
      (footprint "eagle-import:R0603-DASHES")
      (fields (field (name "PARTNO") "ERJ-3GEYJ103V"))
      (libsource (lib "eagle-import") (part "hh2019_rev0_1_0_dev_R0603-DASHES"))
    )
    (comp (ref "R9")
      (value "10k")
      (footprint "eagle-import:R0603-DASHES")
      (fields (field (name "PARTNO") "ERJ-3GEYJ103V"))
      (libsource (lib "eagle-import") (part "R0603-DASHES"))
    )
    (comp (ref "R10")
      (value "10k")
      (footprint "eagle-import:R0603-DASHES")
      (fields (field (name "PARTNO") "ERJ-3GEYJ103V"))
      (libsource (lib "eagle-import") (part "R0603-DASHES"))
    )
    (comp (ref "R23")
      (value "4k7")
      (footprint "eagle-import:R0603-DASHES")
      (fields (field (name "PARTNO") "ERJ-3GEYJ103V"))
      (libsource (lib "eagle-import") (part "hh2019_rev0_1_0_dev_R0603-DASHES"))
    )
    (comp (ref "R24")
      (value "4k7")
      (footprint "eagle-import:R0603-DASHES")
      (fields (field (name "PARTNO") "ERJ-3GEYJ103V"))
      (libsource (lib "eagle-import") (part "hh2019_rev0_1_0_dev_R0603-DASHES"))
    )
    (comp (ref "R29")
      (value "1.2k")
      (footprint "eagle-import:R0603-DASHES")
      (fields (field (name "PARTNO") "ERJ-3GEYJ222V"))
      (libsource (lib "eagle-import") (part "hh2019_rev0_1_0_dev_R0603-DASHES"))
    )
    (comp (ref "R30")
      (value "0R27 1/4W")
      (footprint "eagle-import:R1206")
      (fields (field (name "PARTNO") "ERJ-3GEYJ154V"))
      (libsource (lib "eagle-import") (part "R-EU_R1206"))
    )
    (comp (ref "R32")
      (value "10k")
      (footprint "eagle-import:R0603-DASHES")
      (fields (field (name "PARTNO") "ERJ-3GEYJ154V"))
      (libsource (lib "eagle-import") (part "hh2019_rev0_1_0_dev_R0603-DASHES"))
    )
    (comp (ref "R35")
      (value "1.2k")
      (footprint "eagle-import:R0603-DASHES")
      (fields (field (name "PARTNO") "ERJ-3GEYJ222V"))
      (libsource (lib "eagle-import") (part "hh2019_rev0_1_0_dev_R0603-DASHES"))
    )
    (comp (ref "R36")
      (value "100k")
      (footprint "eagle-import:R0603-DASHES")
      (fields (field (name "PARTNO") "ERJ-3GEYJ104V"))
      (libsource (lib "eagle-import") (part "hh2019_rev0_1_0_dev_R0603-DASHES"))
    )
    (comp (ref "R37")
      (value "75k 1%")
      (footprint "eagle-import:R0603-DASHES")
      (fields (field (name "PARTNO") "ERJ-3GEYJ104V"))
      (libsource (lib "eagle-import") (part "hh2019_rev0_1_0_dev_R0603-DASHES"))
    )
    (comp (ref "SJ3")
      (value "JUMPER-PAD-2-NOYES_SILK")
      (footprint "eagle-import:PAD-JUMPER-2-NO_YES_SILK")
      (fields (field (name "PARTNO") "NAP"))
      (libsource (lib "eagle-import") (part "JUMPER-PAD-2-NOYES_SILK"))
    )
    (comp (ref "T1")
      (value "MOSFET-PCHANNEL")
      (footprint "eagle-import:SOT23-3")
      (libsource (lib "eagle-import") (part "MOSFET-PCHANNEL"))
    )
    (comp (ref "T2")
      (value "MOSFET-PCHANNEL")
      (footprint "eagle-import:SOT23-3")
      (libsource (lib "eagle-import") (part "MOSFET-PCHANNEL"))
    )
    (comp (ref "TOUCH_A")
      (value "TOUCHROUND")
      (footprint "eagle-import:TOUCH_BUTTON")
      (fields (field (name "PARTNO") "NAP"))
      (libsource (lib "eagle-import") (part "TOUCHROUND"))
    )
    (comp (ref "TOUCH_B")
      (value "TOUCHROUND")
      (footprint "eagle-import:TOUCH_BUTTON")
      (fields (field (name "PARTNO") "NAP"))
      (libsource (lib "eagle-import") (part "TOUCHROUND"))
    )
    (comp (ref "TOUCH_SEL")
      (value "TOUCH_CROSS")
      (footprint "eagle-import:TOUCH_CROSS")
      (fields (field (name "PARTNO") "NAP"))
      (libsource (lib "eagle-import") (part "TOUCH_CROSS"))
    )
    (comp (ref "TOUCH_SELECT")
      (value "TOUCHSELECT")
      (footprint "eagle-import:TOUCH_SELECT")
      (libsource (lib "eagle-import") (part "TOUCHSELECT"))
    )
    (comp (ref "TOUCH_START")
      (value "TOUCHSELECT")
      (footprint "eagle-import:TOUCH_SELECT")
      (libsource (lib "eagle-import") (part "TOUCHSELECT"))
    )
    (comp (ref "TP1")
      (value "TEST-POINT3")
      (footprint "eagle-import:PAD.03X.03")
      (fields (field (name "PARTNO") "NAP"))
      (libsource (lib "eagle-import") (part "TEST-POINT3"))
    )
    (comp (ref "TP2")
      (value "TEST-POINT3")
      (footprint "eagle-import:PAD.03X.03")
      (fields (field (name "PARTNO") "NAP"))
      (libsource (lib "eagle-import") (part "TEST-POINT3"))
    )
    (comp (ref "TP3")
      (value "TEST-POINT3")
      (footprint "eagle-import:PAD.03X.03")
      (fields (field (name "PARTNO") "NAP"))
      (libsource (lib "eagle-import") (part "TEST-POINT3"))
    )
    (comp (ref "TP100")
      (value "TEST-POINT3")
      (footprint "eagle-import:PAD.03X.03")
      (fields (field (name "PARTNO") "NAP"))
      (libsource (lib "eagle-import") (part "TEST-POINT3"))
    )
    (comp (ref "TP101")
      (value "TEST-POINT3")
      (footprint "eagle-import:PAD.03X.03")
      (fields (field (name "PARTNO") "NAP"))
      (libsource (lib "eagle-import") (part "TEST-POINT3"))
    )
    (comp (ref "U1")
      (value "MPR121QR2")
      (footprint "eagle-import:QFN40P300X300X60-20N")
      (libsource (lib "eagle-import") (part "MPR121QR2"))
    )
    (comp (ref "X3")
      (value "610X12243021")
      (footprint "eagle-import:610X12243021")
      (fields (field (name "PARTNO") "517-153208-2020-TB"))
      (libsource (lib "eagle-import") (part "610X12243021"))
    )
    (comp (ref "X4")
      (value "JST-PH3")
      (footprint "eagle-import:JST-PH3")
      (libsource (lib "eagle-import") (part "JST-PH3"))
    )
    (comp (ref "$$U$1")
      (value "VIA")
      (footprint "eagle-import:VIA")
      (fields (field (name "PARTNO") "NAP"))
      (libsource (lib "eagle-import") (part "VIA"))
    )
    (comp (ref "$$U$2")
      (value "VIA")
      (footprint "eagle-import:VIA")
      (fields (field (name "PARTNO") "NAP"))
      (libsource (lib "eagle-import") (part "VIA"))
    )
    (comp (ref "$$U$3")
      (value "VIA")
      (footprint "eagle-import:VIA")
      (fields (field (name "PARTNO") "NAP"))
      (libsource (lib "eagle-import") (part "VIA"))
    )
    (comp (ref "$$U$4")
      (value "VIA")
      (footprint "eagle-import:VIA")
      (fields (field (name "PARTNO") "NAP"))
      (libsource (lib "eagle-import") (part "VIA"))
    )
    (comp (ref "$$U$5")
      (value "VIA")
      (footprint "eagle-import:VIA")
      (fields (field (name "PARTNO") "NAP"))
      (libsource (lib "eagle-import") (part "VIA"))
    )
    (comp (ref "$$U$6")
      (value "VIA")
      (footprint "eagle-import:VIA")
      (fields (field (name "PARTNO") "NAP"))
      (libsource (lib "eagle-import") (part "VIA"))
    )
    (comp (ref "$$U$7")
      (value "VIA")
      (footprint "eagle-import:VIA")
      (fields (field (name "PARTNO") "NAP"))
      (libsource (lib "eagle-import") (part "VIA"))
    )
    (comp (ref "$$U$8")
      (value "VIA")
      (footprint "eagle-import:VIA")
      (fields (field (name "PARTNO") "NAP"))
      (libsource (lib "eagle-import") (part "VIA"))
    )
    (comp (ref "$$U$9")
      (value "VIA")
      (footprint "eagle-import:VIA")
      (fields (field (name "PARTNO") "NAP"))
      (libsource (lib "eagle-import") (part "VIA"))
    )
    (comp (ref "C10")
      (value "100n")
      (footprint "eagle-import:C0603-DASHES")
      (fields (field (name "PARTNO") "GRM188R71H104KA93D"))
      (libsource (lib "eagle-import") (part "C0603-DASHES"))
    )
    (comp (ref "C16")
      (value "100n")
      (footprint "eagle-import:C0603-DASHES")
      (fields (field (name "PARTNO") "GRM188R71H104KA93D"))
      (libsource (lib "eagle-import") (part "C0603-DASHES"))
    )
    (comp (ref "R6")
      (value "100k")
      (footprint "eagle-import:R0603-DASHES")
      (fields (field (name "PARTNO") "ERJ-3GEYJ104V"))
      (libsource (lib "eagle-import") (part "hh2019_rev0_1_0_dev_R0603-DASHES"))
    )
    (comp (ref "R7")
      (value "220k")
      (footprint "eagle-import:R0603-DASHES")
      (fields (field (name "PARTNO") "ERJ-3GEYJ224V"))
      (libsource (lib "eagle-import") (part "hh2019_rev0_1_0_dev_R0603-DASHES"))
    )
    (comp (ref "R20")
      (value "100k")
      (footprint "eagle-import:R0603-DASHES")
      (fields (field (name "PARTNO") "ERJ-3GEYJ104V"))
      (libsource (lib "eagle-import") (part "hh2019_rev0_1_0_dev_R0603-DASHES"))
    )
    (comp (ref "R21")
      (value "220k")
      (footprint "eagle-import:R0603-DASHES")
      (fields (field (name "PARTNO") "ERJ-3GEYJ224V"))
      (libsource (lib "eagle-import") (part "hh2019_rev0_1_0_dev_R0603-DASHES"))
    )
    (comp (ref "TP102")
      (value "TEST-POINT3")
      (footprint "eagle-import:PAD.03X.03")
      (fields (field (name "PARTNO") "NAP"))
      (libsource (lib "eagle-import") (part "TEST-POINT3"))
    )
    (comp (ref "TP110")
      (value "TEST-POINT3")
      (footprint "eagle-import:PAD.03X.03")
      (fields (field (name "PARTNO") "NAP"))
      (libsource (lib "eagle-import") (part "TEST-POINT3"))
    )
    (comp (ref "TP112")
      (value "TEST-POINT3")
      (footprint "eagle-import:PAD.03X.03")
      (fields (field (name "PARTNO") "NAP"))
      (libsource (lib "eagle-import") (part "TEST-POINT3"))
    )
    (comp (ref "TP114")
      (value "TEST-POINT3")
      (footprint "eagle-import:PAD.03X.03")
      (fields (field (name "PARTNO") "NAP"))
      (libsource (lib "eagle-import") (part "TEST-POINT3"))
    )
    (comp (ref "TP115")
      (value "TEST-POINT3")
      (footprint "eagle-import:PAD.03X.03")
      (fields (field (name "PARTNO") "NAP"))
      (libsource (lib "eagle-import") (part "TEST-POINT3"))
    )
    (comp (ref "TP116")
      (value "TEST-POINT3")
      (footprint "eagle-import:PAD.03X.03")
      (fields (field (name "PARTNO") "NAP"))
      (libsource (lib "eagle-import") (part "TEST-POINT3"))
    )
    (comp (ref "TP117")
      (value "TEST-POINT3")
      (footprint "eagle-import:PAD.03X.03")
      (fields (field (name "PARTNO") "NAP"))
      (libsource (lib "eagle-import") (part "TEST-POINT3"))
    )
    (comp (ref "TP119")
      (value "TEST-POINT3")
      (footprint "eagle-import:PAD.03X.03")
      (fields (field (name "PARTNO") "NAP"))
      (libsource (lib "eagle-import") (part "TEST-POINT3"))
    )
    (comp (ref "TP120")
      (value "TEST-POINT3")
      (footprint "eagle-import:PAD.03X.03")
      (fields (field (name "PARTNO") "NAP"))
      (libsource (lib "eagle-import") (part "TEST-POINT3"))
    )
    (comp (ref "TP121")
      (value "TEST-POINT3")
      (footprint "eagle-import:PAD.03X.03")
      (fields (field (name "PARTNO") "NAP"))
      (libsource (lib "eagle-import") (part "TEST-POINT3"))
    )
    (comp (ref "TP122")
      (value "TEST-POINT3")
      (footprint "eagle-import:PAD.03X.03")
      (fields (field (name "PARTNO") "NAP"))
      (libsource (lib "eagle-import") (part "TEST-POINT3"))
    )
    (comp (ref "TP129")
      (value "TEST-POINT3")
      (footprint "eagle-import:PAD.03X.03")
      (fields (field (name "PARTNO") "NAP"))
      (libsource (lib "eagle-import") (part "TEST-POINT3"))
    )
    (comp (ref "TP133")
      (value "TEST-POINT3")
      (footprint "eagle-import:PAD.03X.03")
      (fields (field (name "PARTNO") "NAP"))
      (libsource (lib "eagle-import") (part "TEST-POINT3"))
    )
    (comp (ref "TP134")
      (value "TEST-POINT3")
      (footprint "eagle-import:PAD.03X.03")
      (fields (field (name "PARTNO") "NAP"))
      (libsource (lib "eagle-import") (part "TEST-POINT3"))
    )
    (comp (ref "TP135")
      (value "TEST-POINT3")
      (footprint "eagle-import:PAD.03X.03")
      (fields (field (name "PARTNO") "NAP"))
      (libsource (lib "eagle-import") (part "TEST-POINT3"))
    )
    (comp (ref "TP136")
      (value "TEST-POINT3")
      (footprint "eagle-import:PAD.03X.03")
      (fields (field (name "PARTNO") "NAP"))
      (libsource (lib "eagle-import") (part "TEST-POINT3"))
    )
    (comp (ref "TP137")
      (value "TEST-POINT3")
      (footprint "eagle-import:PAD.03X.03")
      (fields (field (name "PARTNO") "NAP"))
      (libsource (lib "eagle-import") (part "TEST-POINT3"))
    )
    (comp (ref "TP138")
      (value "TEST-POINT3")
      (footprint "eagle-import:PAD.03X.03")
      (fields (field (name "PARTNO") "NAP"))
      (libsource (lib "eagle-import") (part "TEST-POINT3"))
    )
    (comp (ref "TP140")
      (value "TEST-POINT3")
      (footprint "eagle-import:PAD.03X.03")
      (fields (field (name "PARTNO") "NAP"))
      (libsource (lib "eagle-import") (part "TEST-POINT3"))
    )
    (comp (ref "U$2")
      (value "VIA")
      (footprint "eagle-import:VIA")
      (fields (field (name "PARTNO") "NAP"))
      (libsource (lib "eagle-import") (part "VIA"))
    )
    (comp (ref "U$3")
      (value "VIA")
      (footprint "eagle-import:VIA")
      (fields (field (name "PARTNO") "NAP"))
      (libsource (lib "eagle-import") (part "VIA"))
    )
    (comp (ref "U$4")
      (value "VIA")
      (footprint "eagle-import:VIA")
      (fields (field (name "PARTNO") "NAP"))
      (libsource (lib "eagle-import") (part "VIA"))
    )
    (comp (ref "U$5")
      (value "VIA")
      (footprint "eagle-import:VIA")
      (fields (field (name "PARTNO") "NAP"))
      (libsource (lib "eagle-import") (part "VIA"))
    )
    (comp (ref "U$6")
      (value "VIA")
      (footprint "eagle-import:VIA")
      (fields (field (name "PARTNO") "NAP"))
      (libsource (lib "eagle-import") (part "VIA"))
    )
    (comp (ref "U$10")
      (value "VIA")
      (footprint "eagle-import:VIA")
      (fields (field (name "PARTNO") "NAP"))
      (libsource (lib "eagle-import") (part "VIA"))
    )
    (comp (ref "U$11")
      (value "VIA")
      (footprint "eagle-import:VIA")
      (fields (field (name "PARTNO") "NAP"))
      (libsource (lib "eagle-import") (part "VIA"))
    )
    (comp (ref "U$12")
      (value "VIA")
      (footprint "eagle-import:VIA")
      (fields (field (name "PARTNO") "NAP"))
      (libsource (lib "eagle-import") (part "VIA"))
    )
    (comp (ref "U$13")
      (value "VIA")
      (footprint "eagle-import:VIA")
      (fields (field (name "PARTNO") "NAP"))
      (libsource (lib "eagle-import") (part "VIA"))
    )
    (comp (ref "U$14")
      (value "VIA")
      (footprint "eagle-import:VIA")
      (fields (field (name "PARTNO") "NAP"))
      (libsource (lib "eagle-import") (part "VIA"))
    )
    (comp (ref "U$15")
      (value "VIA")
      (footprint "eagle-import:VIA")
      (fields (field (name "PARTNO") "NAP"))
      (libsource (lib "eagle-import") (part "VIA"))
    )
    (comp (ref "U$16")
      (value "VIA")
      (footprint "eagle-import:VIA")
      (fields (field (name "PARTNO") "NAP"))
      (libsource (lib "eagle-import") (part "VIA"))
    )
    (comp (ref "U$17")
      (value "VIA")
      (footprint "eagle-import:VIA")
      (fields (field (name "PARTNO") "NAP"))
      (libsource (lib "eagle-import") (part "VIA"))
    )
    (comp (ref "U$18")
      (value "VIA")
      (footprint "eagle-import:VIA")
      (fields (field (name "PARTNO") "NAP"))
      (libsource (lib "eagle-import") (part "VIA"))
    )
    (comp (ref "U$19")
      (value "VIA")
      (footprint "eagle-import:VIA")
      (fields (field (name "PARTNO") "NAP"))
      (libsource (lib "eagle-import") (part "VIA"))
    )
    (comp (ref "U$20")
      (value "VIA")
      (footprint "eagle-import:VIA")
      (fields (field (name "PARTNO") "NAP"))
      (libsource (lib "eagle-import") (part "VIA"))
    )
    (comp (ref "U$21")
      (value "VIA")
      (footprint "eagle-import:VIA")
      (fields (field (name "PARTNO") "NAP"))
      (libsource (lib "eagle-import") (part "VIA"))
    )
    (comp (ref "U$22")
      (value "VIA")
      (footprint "eagle-import:VIA")
      (fields (field (name "PARTNO") "NAP"))
      (libsource (lib "eagle-import") (part "VIA"))
    )
    (comp (ref "U$23")
      (value "VIA")
      (footprint "eagle-import:VIA")
      (fields (field (name "PARTNO") "NAP"))
      (libsource (lib "eagle-import") (part "VIA"))
    )
  )
  (nets
    (net (code "1") (name "+3V3") (class "Default")
      (node (ref "C17") (pin "1") (pinfunction "1_1") (pintype "passive"))
      (node (ref "C20") (pin "1") (pinfunction "1_1") (pintype "passive"))
      (node (ref "C22") (pin "1") (pinfunction "1_1") (pintype "passive"))
      (node (ref "C26") (pin "1") (pinfunction "1_1") (pintype "passive"))
      (node (ref "C27") (pin "1") (pinfunction "1_1") (pintype "passive"))
      (node (ref "C30") (pin "1") (pinfunction "1_1") (pintype "passive"))
      (node (ref "C37") (pin "1") (pinfunction "1_1") (pintype "passive"))
      (node (ref "C39") (pin "1") (pinfunction "1_1") (pintype "passive"))
      (node (ref "C43") (pin "1") (pinfunction "1_1") (pintype "passive"))
      (node (ref "C44") (pin "1") (pinfunction "1_1") (pintype "passive"))
      (node (ref "C46") (pin "1") (pinfunction "1_1") (pintype "passive"))
      (node (ref "IC2") (pin "4") (pinfunction "OUT_4") (pintype "passive"))
      (node (ref "IC3") (pin "2") (pinfunction "VCC_2") (pintype "power_in"))
      (node (ref "L1") (pin "1") (pinfunction "1_1") (pintype "passive"))
      (node (ref "R1") (pin "2") (pinfunction "2_2") (pintype "passive"))
      (node (ref "R16") (pin "2") (pinfunction "2_2") (pintype "passive"))
      (node (ref "R22") (pin "1") (pinfunction "1_1") (pintype "passive"))
      (node (ref "R23") (pin "1") (pinfunction "1_1") (pintype "passive"))
      (node (ref "R24") (pin "1") (pinfunction "1_1") (pintype "passive"))
      (node (ref "R26") (pin "1") (pinfunction "1_1") (pintype "passive"))
      (node (ref "R28") (pin "2") (pinfunction "2_2") (pintype "passive"))
      (node (ref "R36") (pin "2") (pinfunction "2_2") (pintype "passive"))
      (node (ref "T3") (pin "2") (pinfunction "S_2") (pintype "passive"))
      (node (ref "TP119") (pin "P$1") (pinfunction "1_P$1") (pintype "bidirectional"))
      (node (ref "U1") (pin "20") (pinfunction "V_DD_20") (pintype "power_in"))
      (node (ref "X1") (pin "10") (pinfunction "10_10") (pintype "passive"))
      (node (ref "X1") (pin "9") (pinfunction "9_9") (pintype "passive"))
    )
    (net (code "2") (name "+5V") (class "Default")
      (node (ref "C11") (pin "1") (pinfunction "1_1") (pintype "passive"))
      (node (ref "C9") (pin "1") (pinfunction "1_1") (pintype "passive"))
      (node (ref "D1") (pin "C") (pinfunction "C_C") (pintype "passive"))
      (node (ref "D3") (pin "A") (pinfunction "A_A") (pintype "passive"))
      (node (ref "F1") (pin "2") (pinfunction "2_2") (pintype "bidirectional"))
      (node (ref "IC1") (pin "7") (pinfunction "REGIN_7") (pintype "passive"))
      (node (ref "IC1") (pin "8") (pinfunction "VBUS_8") (pintype "input"))
      (node (ref "R30") (pin "1") (pinfunction "1_1") (pintype "passive"))
      (node (ref "R4") (pin "2") (pinfunction "2_2") (pintype "passive"))
      (node (ref "R7") (pin "2") (pinfunction "2_2") (pintype "passive"))
      (node (ref "T1") (pin "1") (pinfunction "G_1") (pintype "passive"))
      (node (ref "TP112") (pin "P$1") (pinfunction "1_P$1") (pintype "bidirectional"))
    )
    (net (code "3") (name "3V3_SWITCHED") (class "Default")
      (node (ref "C12") (pin "1") (pinfunction "1_1") (pintype "passive"))
      (node (ref "C31") (pin "1") (pinfunction "1_1") (pintype "passive"))
      (node (ref "C40") (pin "1") (pinfunction "1_1") (pintype "passive"))
      (node (ref "C41") (pin "1") (pinfunction "1_1") (pintype "passive"))
      (node (ref "C7") (pin "1") (pinfunction "1_1") (pintype "passive"))
      (node (ref "R17") (pin "2") (pinfunction "2_2") (pintype "passive"))
      (node (ref "R25") (pin "2") (pinfunction "2_2") (pintype "passive"))
      (node (ref "R31") (pin "1") (pinfunction "1_1") (pintype "passive"))
      (node (ref "R5") (pin "2") (pinfunction "2_2") (pintype "passive"))
      (node (ref "R8") (pin "2") (pinfunction "2_2") (pintype "passive"))
      (node (ref "T3") (pin "3") (pinfunction "D_3") (pintype "passive"))
      (node (ref "TP116") (pin "P$1") (pinfunction "1_P$1") (pintype "bidirectional"))
      (node (ref "X2") (pin "4") (pinfunction "VCC_4") (pintype "bidirectional"))
      (node (ref "X3") (pin "12") (pinfunction "1_12") (pintype "passive"))
    )
    (net (code "4") (name "CHRG_STAT") (class "Default")
      (node (ref "IC4") (pin "7") (pinfunction "CHRG_7") (pintype "bidirectional"))
      (node (ref "R36") (pin "1") (pinfunction "1_1") (pintype "passive"))
      (node (ref "U1") (pin "17") (pinfunction "ELE9_17") (pintype "output"))
    )
    (net (code "5") (name "ESP32_FLASH") (class "Default")
      (node (ref "D2") (pin "C") (pinfunction "C_C") (pintype "passive"))
      (node (ref "IC3") (pin "25") (pinfunction "IO0_25") (pintype "bidirectional"))
      (node (ref "Q4") (pin "3") (pinfunction "C_3") (pintype "passive"))
      (node (ref "R16") (pin "1") (pinfunction "1_1") (pintype "passive"))
      (node (ref "S2") (pin "3") (pinfunction "2_3") (pintype "passive"))
      (node (ref "TP120") (pin "P$1") (pinfunction "1_P$1") (pintype "bidirectional"))
    )
    (net (code "6") (name "ESP32_RX") (class "Default")
      (node (ref "D4") (pin "C") (pinfunction "C_C") (pintype "passive"))
      (node (ref "IC1") (pin "26") (pinfunction "TXD_26") (pintype "output"))
      (node (ref "IC3") (pin "34") (pinfunction "RXD0_34") (pintype "bidirectional"))
      (node (ref "TP133") (pin "P$1") (pinfunction "1_P$1") (pintype "bidirectional"))
    )
    (net (code "7") (name "ESP32_TX") (class "Default")
      (node (ref "D5") (pin "C") (pinfunction "C_C") (pintype "passive"))
      (node (ref "IC1") (pin "25") (pinfunction "RXD_25") (pintype "input"))
      (node (ref "IC3") (pin "35") (pinfunction "TXD0_35") (pintype "bidirectional"))
      (node (ref "TP134") (pin "P$1") (pinfunction "1_P$1") (pintype "bidirectional"))
    )
    (net (code "8") (name "ESP32_~{RESET}") (class "Default")
      (node (ref "IC3") (pin "3") (pinfunction "EN_3") (pintype "bidirectional"))
      (node (ref "Q3") (pin "3") (pinfunction "C_3") (pintype "passive"))
      (node (ref "R22") (pin "2") (pinfunction "2_2") (pintype "passive"))
      (node (ref "S1") (pin "3") (pinfunction "2_3") (pintype "passive"))
      (node (ref "TP121") (pin "P$1") (pinfunction "1_P$1") (pintype "bidirectional"))
    )
    (net (code "9") (name "EXTIO-0") (class "Default")
      (node (ref "IC3") (pin "9") (pinfunction "IO33_9") (pintype "bidirectional"))
      (node (ref "X3") (pin "3") (pinfunction "10_3") (pintype "passive"))
    )
    (net (code "10") (name "EXTIO-1") (class "Default")
      (node (ref "IC3") (pin "27") (pinfunction "IO16_27") (pintype "bidirectional"))
      (node (ref "X3") (pin "4") (pinfunction "9_4") (pintype "passive"))
    )
    (net (code "11") (name "EXTIO-2") (class "Default")
      (node (ref "IC3") (pin "28") (pinfunction "IO17_28") (pintype "bidirectional"))
      (node (ref "X3") (pin "5") (pinfunction "8_5") (pintype "passive"))
    )
    (net (code "12") (name "EXTIO-3") (class "Default")
      (node (ref "IC3") (pin "26") (pinfunction "IO4_26") (pintype "bidirectional"))
      (node (ref "X3") (pin "9") (pinfunction "4_9") (pintype "passive"))
    )
    (net (code "13") (name "EXTIO-4") (class "Default")
      (node (ref "IC3") (pin "14") (pinfunction "IO12_14") (pintype "bidirectional"))
      (node (ref "X3") (pin "10") (pinfunction "3_10") (pintype "passive"))
    )
    (net (code "14") (name "GDR") (class "Default")
      (node (ref "Q5") (pin "1") (pinfunction "G_1") (pintype "passive"))
      (node (ref "TP124") (pin "P$1") (pinfunction "1_P$1") (pintype "bidirectional"))
      (node (ref "X1") (pin "23") (pinfunction "23_23") (pintype "passive"))
    )
    (net (code "15") (name "GND") (class "Default")
      (node (ref "$$U$1") (pin "P$1") (pinfunction "P$1_P$1") (pintype "bidirectional"))
      (node (ref "$$U$2") (pin "P$1") (pinfunction "P$1_P$1") (pintype "bidirectional"))
      (node (ref "$$U$3") (pin "P$1") (pinfunction "P$1_P$1") (pintype "bidirectional"))
      (node (ref "$$U$4") (pin "P$1") (pinfunction "P$1_P$1") (pintype "bidirectional"))
      (node (ref "$$U$5") (pin "P$1") (pinfunction "P$1_P$1") (pintype "bidirectional"))
      (node (ref "$$U$6") (pin "P$1") (pinfunction "P$1_P$1") (pintype "bidirectional"))
      (node (ref "$$U$7") (pin "P$1") (pinfunction "P$1_P$1") (pintype "bidirectional"))
      (node (ref "$$U$8") (pin "P$1") (pinfunction "P$1_P$1") (pintype "bidirectional"))
      (node (ref "$$U$9") (pin "P$1") (pinfunction "P$1_P$1") (pintype "bidirectional"))
      (node (ref "C1") (pin "1") (pinfunction "1_1") (pintype "passive"))
      (node (ref "C10") (pin "2") (pinfunction "2_2") (pintype "passive"))
      (node (ref "C11") (pin "2") (pinfunction "2_2") (pintype "passive"))
      (node (ref "C12") (pin "2") (pinfunction "2_2") (pintype "passive"))
      (node (ref "C13") (pin "2") (pinfunction "2_2") (pintype "passive"))
      (node (ref "C14") (pin "2") (pinfunction "2_2") (pintype "passive"))
      (node (ref "C15") (pin "2") (pinfunction "2_2") (pintype "passive"))
      (node (ref "C16") (pin "2") (pinfunction "2_2") (pintype "passive"))
      (node (ref "C17") (pin "2") (pinfunction "2_2") (pintype "passive"))
      (node (ref "C18") (pin "2") (pinfunction "2_2") (pintype "passive"))
      (node (ref "C19") (pin "1") (pinfunction "1_1") (pintype "passive"))
      (node (ref "C2") (pin "1") (pinfunction "1_1") (pintype "passive"))
      (node (ref "C20") (pin "2") (pinfunction "2_2") (pintype "passive"))
      (node (ref "C21") (pin "1") (pinfunction "1_1") (pintype "passive"))
      (node (ref "C22") (pin "2") (pinfunction "2_2") (pintype "passive"))
      (node (ref "C23") (pin "1") (pinfunction "1_1") (pintype "passive"))
      (node (ref "C24") (pin "2") (pinfunction "2_2") (pintype "passive"))
      (node (ref "C26") (pin "2") (pinfunction "2_2") (pintype "passive"))
      (node (ref "C27") (pin "2") (pinfunction "2_2") (pintype "passive"))
      (node (ref "C28") (pin "1") (pinfunction "1_1") (pintype "passive"))
      (node (ref "C29") (pin "1") (pinfunction "1_1") (pintype "passive"))
      (node (ref "C3") (pin "1") (pinfunction "1_1") (pintype "passive"))
      (node (ref "C30") (pin "2") (pinfunction "2_2") (pintype "passive"))
      (node (ref "C31") (pin "2") (pinfunction "2_2") (pintype "passive"))
      (node (ref "C32") (pin "1") (pinfunction "1_1") (pintype "passive"))
      (node (ref "C33") (pin "1") (pinfunction "1_1") (pintype "passive"))
      (node (ref "C34") (pin "2") (pinfunction "2_2") (pintype "passive"))
      (node (ref "C35") (pin "1") (pinfunction "1_1") (pintype "passive"))
      (node (ref "C36") (pin "1") (pinfunction "1_1") (pintype "passive"))
      (node (ref "C37") (pin "2") (pinfunction "2_2") (pintype "passive"))
      (node (ref "C38") (pin "1") (pinfunction "1_1") (pintype "passive"))
      (node (ref "C39") (pin "2") (pinfunction "2_2") (pintype "passive"))
      (node (ref "C4") (pin "1") (pinfunction "1_1") (pintype "passive"))
      (node (ref "C40") (pin "2") (pinfunction "2_2") (pintype "passive"))
      (node (ref "C41") (pin "2") (pinfunction "2_2") (pintype "passive"))
      (node (ref "C42") (pin "2") (pinfunction "2_2") (pintype "passive"))
      (node (ref "C43") (pin "2") (pinfunction "2_2") (pintype "passive"))
      (node (ref "C44") (pin "2") (pinfunction "2_2") (pintype "passive"))
      (node (ref "C45") (pin "2") (pinfunction "2_2") (pintype "passive"))
      (node (ref "C46") (pin "2") (pinfunction "2_2") (pintype "passive"))
      (node (ref "C5") (pin "1") (pinfunction "1_1") (pintype "passive"))
      (node (ref "C6") (pin "1") (pinfunction "1_1") (pintype "passive"))
      (node (ref "C7") (pin "2") (pinfunction "2_2") (pintype "passive"))
      (node (ref "C8") (pin "2") (pinfunction "2_2") (pintype "passive"))
      (node (ref "C9") (pin "2") (pinfunction "2_2") (pintype "passive"))
      (node (ref "D1") (pin "A") (pinfunction "A_A") (pintype "passive"))
      (node (ref "D100") (pin "3") (pinfunction "VSS_3") (pintype "power_in"))
      (node (ref "D101") (pin "3") (pinfunction "VSS_3") (pintype "power_in"))
      (node (ref "D102") (pin "3") (pinfunction "VSS_3") (pintype "power_in"))
      (node (ref "D103") (pin "3") (pinfunction "VSS_3") (pintype "power_in"))
      (node (ref "D104") (pin "3") (pinfunction "VSS_3") (pintype "power_in"))
      (node (ref "D105") (pin "3") (pinfunction "VSS_3") (pintype "power_in"))
      (node (ref "D6") (pin "C") (pinfunction "C_C") (pintype "passive"))
      (node (ref "D7") (pin "C") (pinfunction "C_C") (pintype "passive"))
      (node (ref "IC1") (pin "3") (pinfunction "GND_3") (pintype "power_in"))
      (node (ref "IC1") (pin "EXP") (pinfunction "GND_EXP") (pintype "power_in"))
      (node (ref "IC1") (pin "M") (pinfunction "GND_M") (pintype "power_in"))
      (node (ref "IC2") (pin "1") (pinfunction "ADJ_1") (pintype "input"))
      (node (ref "IC3") (pin "0") (pinfunction "GND_0") (pintype "power_in"))
      (node (ref "IC3") (pin "1") (pinfunction "GND_1") (pintype "power_in"))
      (node (ref "IC3") (pin "15") (pinfunction "GND_15") (pintype "power_in"))
      (node (ref "IC3") (pin "38") (pinfunction "GND_38") (pintype "power_in"))
      (node (ref "IC4") (pin "3") (pinfunction "GND_3") (pintype "bidirectional"))
      (node (ref "Q1") (pin "2") (pinfunction "E_2") (pintype "passive"))
      (node (ref "Q2") (pin "2") (pinfunction "E_2") (pintype "passive"))
      (node (ref "Q6") (pin "2") (pinfunction "E_2") (pintype "passive"))
      (node (ref "R19") (pin "2") (pinfunction "2_2") (pintype "passive"))
      (node (ref "R20") (pin "1") (pinfunction "1_1") (pintype "passive"))
      (node (ref "R35") (pin "2") (pinfunction "2_2") (pintype "passive"))
      (node (ref "R37") (pin "1") (pinfunction "1_1") (pintype "passive"))
      (node (ref "R4") (pin "1") (pinfunction "1_1") (pintype "passive"))
      (node (ref "R6") (pin "1") (pinfunction "1_1") (pintype "passive"))
      (node (ref "S1") (pin "1") (pinfunction "1_1") (pintype "passive"))
      (node (ref "S2") (pin "1") (pinfunction "1_1") (pintype "passive"))
      (node (ref "SJ3") (pin "1") (pinfunction "1_1") (pintype "passive"))
      (node (ref "TP1") (pin "P$1") (pinfunction "1_P$1") (pintype "bidirectional"))
      (node (ref "TP102") (pin "P$1") (pinfunction "1_P$1") (pintype "bidirectional"))
      (node (ref "TP103") (pin "P$1") (pinfunction "1_P$1") (pintype "bidirectional"))
      (node (ref "TP106") (pin "P$1") (pinfunction "1_P$1") (pintype "bidirectional"))
      (node (ref "TP122") (pin "P$1") (pinfunction "1_P$1") (pintype "bidirectional"))
      (node (ref "TP125") (pin "P$1") (pinfunction "1_P$1") (pintype "bidirectional"))
      (node (ref "TP135") (pin "P$1") (pinfunction "1_P$1") (pintype "bidirectional"))
      (node (ref "TP140") (pin "P$1") (pinfunction "1_P$1") (pintype "bidirectional"))
      (node (ref "U$10") (pin "P$1") (pinfunction "P$1_P$1") (pintype "bidirectional"))
      (node (ref "U$11") (pin "P$1") (pinfunction "P$1_P$1") (pintype "bidirectional"))
      (node (ref "U$12") (pin "P$1") (pinfunction "P$1_P$1") (pintype "bidirectional"))
      (node (ref "U$13") (pin "P$1") (pinfunction "P$1_P$1") (pintype "bidirectional"))
      (node (ref "U$14") (pin "P$1") (pinfunction "P$1_P$1") (pintype "bidirectional"))
      (node (ref "U$15") (pin "P$1") (pinfunction "P$1_P$1") (pintype "bidirectional"))
      (node (ref "U$16") (pin "P$1") (pinfunction "P$1_P$1") (pintype "bidirectional"))
      (node (ref "U$17") (pin "P$1") (pinfunction "P$1_P$1") (pintype "bidirectional"))
      (node (ref "U$18") (pin "P$1") (pinfunction "P$1_P$1") (pintype "bidirectional"))
      (node (ref "U$19") (pin "P$1") (pinfunction "P$1_P$1") (pintype "bidirectional"))
      (node (ref "U$2") (pin "P$1") (pinfunction "P$1_P$1") (pintype "bidirectional"))
      (node (ref "U$20") (pin "P$1") (pinfunction "P$1_P$1") (pintype "bidirectional"))
      (node (ref "U$21") (pin "P$1") (pinfunction "P$1_P$1") (pintype "bidirectional"))
      (node (ref "U$22") (pin "P$1") (pinfunction "P$1_P$1") (pintype "bidirectional"))
      (node (ref "U$23") (pin "P$1") (pinfunction "P$1_P$1") (pintype "bidirectional"))
      (node (ref "U$3") (pin "P$1") (pinfunction "P$1_P$1") (pintype "bidirectional"))
      (node (ref "U$4") (pin "P$1") (pinfunction "P$1_P$1") (pintype "bidirectional"))
      (node (ref "U$5") (pin "P$1") (pinfunction "P$1_P$1") (pintype "bidirectional"))
      (node (ref "U$6") (pin "P$1") (pinfunction "P$1_P$1") (pintype "bidirectional"))
      (node (ref "U1") (pin "4") (pinfunction "ADDR_4") (pintype "input"))
      (node (ref "U1") (pin "6") (pinfunction "V_SS_6") (pintype "power_in"))
      (node (ref "USB1") (pin "5") (pinfunction "5_5") (pintype "input"))
      (node (ref "USB1") (pin "GND1") (pinfunction "GND1_GND1") (pintype "bidirectional"))
      (node (ref "USB1") (pin "GND2") (pinfunction "GND2_GND2") (pintype "bidirectional"))
      (node (ref "USB1") (pin "GND3") (pinfunction "GND3_GND3") (pintype "bidirectional"))
      (node (ref "USB1") (pin "GND4") (pinfunction "GND4_GND4") (pintype "bidirectional"))
      (node (ref "X1") (pin "17") (pinfunction "17_17") (pintype "passive"))
      (node (ref "X1") (pin "8") (pinfunction "8_8") (pintype "passive"))
      (node (ref "X2") (pin "6") (pinfunction "GND_6") (pintype "bidirectional"))
      (node (ref "X2") (pin "CD2") (pinfunction "SHIELD_CD2") (pintype "bidirectional"))
      (node (ref "X2") (pin "GND1") (pinfunction "SHIELD_GND1") (pintype "bidirectional"))
      (node (ref "X2") (pin "GND3") (pinfunction "SHIELD_GND3") (pintype "bidirectional"))
      (node (ref "X3") (pin "1") (pinfunction "12_1") (pintype "passive"))
      (node (ref "X3") (pin "11") (pinfunction "2_11") (pintype "passive"))
      (node (ref "X4") (pin "2") (pinfunction "1_2") (pintype "passive"))
    )
    (net (code "16") (name "I2C_INT") (class "Default")
      (node (ref "IC3") (pin "10") (pinfunction "IO25_10") (pintype "bidirectional"))
      (node (ref "R1") (pin "1") (pinfunction "1_1") (pintype "passive"))
      (node (ref "U1") (pin "1") (pinfunction "~{IRQ}_1") (pintype "input"))
    )
    (net (code "17") (name "I2C_SCL") (class "Default")
      (node (ref "IC3") (pin "12") (pinfunction "IO27_12") (pintype "bidirectional"))
      (node (ref "R24") (pin "2") (pinfunction "2_2") (pintype "passive"))
      (node (ref "TP100") (pin "P$1") (pinfunction "1_P$1") (pintype "bidirectional"))
      (node (ref "TP114") (pin "P$1") (pinfunction "1_P$1") (pintype "bidirectional"))
      (node (ref "TP3") (pin "P$1") (pinfunction "1_P$1") (pintype "bidirectional"))
      (node (ref "U1") (pin "2") (pinfunction "SCL_2") (pintype "input"))
      (node (ref "X3") (pin "6") (pinfunction "7_6") (pintype "passive"))
    )
    (net (code "18") (name "I2C_SDA") (class "Default")
      (node (ref "IC3") (pin "11") (pinfunction "IO26_11") (pintype "bidirectional"))
      (node (ref "R23") (pin "2") (pinfunction "2_2") (pintype "passive"))
      (node (ref "TP101") (pin "P$1") (pinfunction "1_P$1") (pintype "bidirectional"))
      (node (ref "TP115") (pin "P$1") (pinfunction "1_P$1") (pintype "bidirectional"))
      (node (ref "TP2") (pin "P$1") (pinfunction "1_P$1") (pintype "bidirectional"))
      (node (ref "U1") (pin "3") (pinfunction "SDA_3") (pintype "input"))
      (node (ref "X3") (pin "7") (pinfunction "6_7") (pintype "passive"))
    )
    (net (code "19") (name "LCD_BUSY") (class "Default")
      (node (ref "IC3") (pin "36") (pinfunction "IO22_36") (pintype "bidirectional"))
      (node (ref "TP118") (pin "P$1") (pinfunction "1_P$1") (pintype "bidirectional"))
      (node (ref "X1") (pin "16") (pinfunction "16_16") (pintype "passive"))
    )
    (net (code "20") (name "LCD_CS") (class "Default")
      (node (ref "IC3") (pin "31") (pinfunction "IO19_31") (pintype "bidirectional"))
      (node (ref "TP109") (pin "P$1") (pinfunction "1_P$1") (pintype "bidirectional"))
      (node (ref "X1") (pin "13") (pinfunction "13_13") (pintype "passive"))
    )
    (net (code "21") (name "LCD_D{slash}~{S}") (class "Default")
      (node (ref "IC3") (pin "33") (pinfunction "IO21_33") (pintype "bidirectional"))
      (node (ref "TP111") (pin "P$1") (pinfunction "1_P$1") (pintype "bidirectional"))
      (node (ref "X1") (pin "14") (pinfunction "14_14") (pintype "passive"))
    )
    (net (code "22") (name "LCD_MOSI") (class "Default")
      (node (ref "IC3") (pin "29") (pinfunction "IO5_29") (pintype "bidirectional"))
      (node (ref "TP107") (pin "P$1") (pinfunction "1_P$1") (pintype "bidirectional"))
      (node (ref "X1") (pin "11") (pinfunction "11_11") (pintype "passive"))
    )
    (net (code "23") (name "LCD_SCK") (class "Default")
      (node (ref "IC3") (pin "30") (pinfunction "IO18_30") (pintype "bidirectional"))
      (node (ref "TP108") (pin "P$1") (pinfunction "1_P$1") (pintype "bidirectional"))
      (node (ref "X1") (pin "12") (pinfunction "12_12") (pintype "passive"))
    )
    (net (code "24") (name "LCD_VDD") (class "Default")
      (node (ref "C42") (pin "1") (pinfunction "1_1") (pintype "passive"))
      (node (ref "R26") (pin "2") (pinfunction "2_2") (pintype "passive"))
      (node (ref "X1") (pin "7") (pinfunction "7_7") (pintype "passive"))
    )
    (net (code "25") (name "LCD_~{RESET}") (class "Default")
      (node (ref "IC3") (pin "37") (pinfunction "IO23_37") (pintype "bidirectional"))
      (node (ref "TP113") (pin "P$1") (pinfunction "1_P$1") (pintype "bidirectional"))
      (node (ref "X1") (pin "15") (pinfunction "15_15") (pintype "passive"))
    )
    (net (code "26") (name "Net-(C25-Pad1)") (class "Default")
      (node (ref "C25") (pin "1") (pinfunction "1_1") (pintype "passive"))
      (node (ref "D7") (pin "A") (pinfunction "A_A") (pintype "passive"))
      (node (ref "D8") (pin "C") (pinfunction "C_C") (pintype "passive"))
    )
    (net (code "27") (name "Net-(D4-PadA)") (class "Default")
      (node (ref "D4") (pin "A") (pinfunction "A_A") (pintype "passive"))
      (node (ref "R3") (pin "1") (pinfunction "1_1") (pintype "passive"))
    )
    (net (code "28") (name "Net-(D5-PadA)") (class "Default")
      (node (ref "D5") (pin "A") (pinfunction "A_A") (pintype "passive"))
      (node (ref "R14") (pin "1") (pinfunction "1_1") (pintype "passive"))
    )
    (net (code "29") (name "Net-(D6-PadA)") (class "Default")
      (node (ref "D6") (pin "A") (pinfunction "A_A") (pintype "passive"))
      (node (ref "R12") (pin "1") (pinfunction "1_1") (pintype "passive"))
    )
    (net (code "30") (name "Net-(D100-DIN)") (class "Default")
      (node (ref "D100") (pin "4") (pinfunction "DIN_4") (pintype "input"))
      (node (ref "D101") (pin "2") (pinfunction "DOUT_2") (pintype "output"))
    )
    (net (code "31") (name "Net-(D101-DIN)") (class "Default")
      (node (ref "D101") (pin "4") (pinfunction "DIN_4") (pintype "input"))
      (node (ref "D102") (pin "2") (pinfunction "DOUT_2") (pintype "output"))
    )
    (net (code "32") (name "Net-(D102-DIN)") (class "Default")
      (node (ref "D102") (pin "4") (pinfunction "DIN_4") (pintype "input"))
      (node (ref "D103") (pin "2") (pinfunction "DOUT_2") (pintype "output"))
    )
    (net (code "33") (name "Net-(D103-DIN)") (class "Default")
      (node (ref "D103") (pin "4") (pinfunction "DIN_4") (pintype "input"))
      (node (ref "D104") (pin "2") (pinfunction "DOUT_2") (pintype "output"))
    )
    (net (code "34") (name "Net-(D104-DIN)") (class "Default")
      (node (ref "D104") (pin "4") (pinfunction "DIN_4") (pintype "input"))
      (node (ref "D105") (pin "2") (pinfunction "DOUT_2") (pintype "output"))
    )
    (net (code "35") (name "Net-(IC1-DTR)") (class "Default")
      (node (ref "IC1") (pin "28") (pinfunction "DTR_28") (pintype "output"))
      (node (ref "Q4") (pin "2") (pinfunction "E_2") (pintype "passive"))
      (node (ref "R18") (pin "1") (pinfunction "1_1") (pintype "passive"))
    )
    (net (code "36") (name "Net-(IC1-RTS)") (class "Default")
      (node (ref "IC1") (pin "24") (pinfunction "RTS_24") (pintype "output"))
      (node (ref "Q3") (pin "2") (pinfunction "E_2") (pintype "passive"))
      (node (ref "R15") (pin "1") (pinfunction "1_1") (pintype "passive"))
    )
    (net (code "37") (name "Net-(IC1-~{RST})") (class "Default")
      (node (ref "IC1") (pin "9") (pinfunction "~{RST}_9") (pintype "bidirectional"))
      (node (ref "R13") (pin "2") (pinfunction "2_2") (pintype "passive"))
    )
    (net (code "38") (name "Net-(IC3-CLK)") (class "Default")
      (node (ref "IC3") (pin "20") (pinfunction "CLK_20") (pintype "bidirectional"))
      (node (ref "TP130") (pin "P$1") (pinfunction "1_P$1") (pintype "bidirectional"))
    )
    (net (code "39") (name "Net-(IC3-CND)") (class "Default")
      (node (ref "IC3") (pin "19") (pinfunction "CND_19") (pintype "bidirectional"))
      (node (ref "TP128") (pin "P$1") (pinfunction "1_P$1") (pintype "bidirectional"))
    )
    (net (code "40") (name "Net-(IC3-SD0)") (class "Default")
      (node (ref "IC3") (pin "21") (pinfunction "SD0_21") (pintype "bidirectional"))
      (node (ref "TP131") (pin "P$1") (pinfunction "1_P$1") (pintype "bidirectional"))
    )
    (net (code "41") (name "Net-(IC3-SD1)") (class "Default")
      (node (ref "IC3") (pin "22") (pinfunction "SD1_22") (pintype "bidirectional"))
      (node (ref "TP132") (pin "P$1") (pinfunction "1_P$1") (pintype "bidirectional"))
    )
    (net (code "42") (name "Net-(IC3-SD2)") (class "Default")
      (node (ref "IC3") (pin "17") (pinfunction "SD2_17") (pintype "bidirectional"))
      (node (ref "TP126") (pin "P$1") (pinfunction "1_P$1") (pintype "bidirectional"))
    )
    (net (code "43") (name "Net-(IC3-SD3)") (class "Default")
      (node (ref "IC3") (pin "18") (pinfunction "SD3_18") (pintype "bidirectional"))
      (node (ref "TP127") (pin "P$1") (pinfunction "1_P$1") (pintype "bidirectional"))
    )
    (net (code "44") (name "Net-(IC3-SENSOR_VN)") (class "Default")
      (node (ref "C29") (pin "2") (pinfunction "2_2") (pintype "passive"))
      (node (ref "IC3") (pin "5") (pinfunction "SENSOR_VN_5") (pintype "bidirectional"))
    )
    (net (code "45") (name "Net-(IC3-SENSOR_VP)") (class "Default")
      (node (ref "C28") (pin "2") (pinfunction "2_2") (pintype "passive"))
      (node (ref "IC3") (pin "4") (pinfunction "SENSOR_VP_4") (pintype "bidirectional"))
    )
    (net (code "46") (name "Net-(IC4-BAT)") (class "Default")
      (node (ref "C34") (pin "1") (pinfunction "1_1") (pintype "passive"))
      (node (ref "F2") (pin "1") (pinfunction "1_1") (pintype "bidirectional"))
      (node (ref "IC4") (pin "5") (pinfunction "BAT_5") (pintype "bidirectional"))
      (node (ref "X4") (pin "3") (pinfunction "1_3") (pintype "passive"))
    )
    (net (code "47") (name "Net-(IC4-CE)") (class "Default")
      (node (ref "C23") (pin "2") (pinfunction "2_2") (pintype "passive"))
      (node (ref "C24") (pin "1") (pinfunction "1_1") (pintype "passive"))
      (node (ref "IC4") (pin "4") (pinfunction "VCC_4") (pintype "bidirectional"))
      (node (ref "IC4") (pin "8") (pinfunction "CE_8") (pintype "bidirectional"))
      (node (ref "R30") (pin "2") (pinfunction "2_2") (pintype "passive"))
      (node (ref "R32") (pin "2") (pinfunction "2_2") (pintype "passive"))
    )
    (net (code "48") (name "Net-(IC4-PROG)") (class "Default")
      (node (ref "IC4") (pin "2") (pinfunction "PROG_2") (pintype "bidirectional"))
      (node (ref "R29") (pin "1") (pinfunction "1_1") (pintype "passive"))
    )
    (net (code "49") (name "Net-(M1-Pad+)") (class "Default")
      (node (ref "M1") (pin "+") (pinfunction "+_+") (pintype "bidirectional"))
      (node (ref "R2") (pin "1") (pinfunction "1_1") (pintype "passive"))
    )
    (net (code "50") (name "Net-(Q1-B)") (class "Default")
      (node (ref "Q1") (pin "1") (pinfunction "B_1") (pintype "passive"))
      (node (ref "R10") (pin "2") (pinfunction "2_2") (pintype "passive"))
    )
    (net (code "51") (name "Net-(Q1-C)") (class "Default")
      (node (ref "Q1") (pin "3") (pinfunction "C_3") (pintype "passive"))
      (node (ref "R9") (pin "1") (pinfunction "1_1") (pintype "passive"))
      (node (ref "T2") (pin "1") (pinfunction "G_1") (pintype "passive"))
    )
    (net (code "52") (name "Net-(Q2-B)") (class "Default")
      (node (ref "Q2") (pin "1") (pinfunction "B_1") (pintype "passive"))
      (node (ref "R11") (pin "1") (pinfunction "1_1") (pintype "passive"))
    )
    (net (code "53") (name "Net-(Q2-C)") (class "Default")
      (node (ref "M1") (pin "-") (pinfunction "-_-") (pintype "bidirectional"))
      (node (ref "Q2") (pin "3") (pinfunction "C_3") (pintype "passive"))
    )
    (net (code "54") (name "Net-(Q3-B)") (class "Default")
      (node (ref "Q3") (pin "1") (pinfunction "B_1") (pintype "passive"))
      (node (ref "R18") (pin "2") (pinfunction "2_2") (pintype "passive"))
    )
    (net (code "55") (name "Net-(Q4-B)") (class "Default")
      (node (ref "Q4") (pin "1") (pinfunction "B_1") (pintype "passive"))
      (node (ref "R15") (pin "2") (pinfunction "2_2") (pintype "passive"))
    )
    (net (code "56") (name "Net-(Q5-D)") (class "Default")
      (node (ref "C25") (pin "2") (pinfunction "2_2") (pintype "passive"))
      (node (ref "D9") (pin "A") (pinfunction "A_A") (pintype "passive"))
      (node (ref "L1") (pin "2") (pinfunction "2_2") (pintype "passive"))
      (node (ref "Q5") (pin "3") (pinfunction "D_3") (pintype "passive"))
    )
    (net (code "57") (name "Net-(Q6-B)") (class "Default")
      (node (ref "Q6") (pin "1") (pinfunction "B_1") (pintype "passive"))
      (node (ref "R27") (pin "2") (pinfunction "2_2") (pintype "passive"))
    )
    (net (code "58") (name "Net-(Q6-C)") (class "Default")
      (node (ref "Q6") (pin "3") (pinfunction "C_3") (pintype "passive"))
      (node (ref "R28") (pin "1") (pinfunction "1_1") (pintype "passive"))
      (node (ref "T3") (pin "1") (pinfunction "G_1") (pintype "passive"))
    )
    (net (code "59") (name "Net-(R29-Pad2)") (class "Default")
      (node (ref "R29") (pin "2") (pinfunction "2_2") (pintype "passive"))
      (node (ref "R35") (pin "1") (pinfunction "1_1") (pintype "passive"))
      (node (ref "SJ3") (pin "2") (pinfunction "2_2") (pintype "passive"))
    )
    (net (code "60") (name "Net-(TOUCH_SEL-DOWN)") (class "Default")
      (node (ref "TOUCH_SEL") (pin "D") (pinfunction "DOWN_D") (pintype "bidirectional"))
      (node (ref "U1") (pin "12") (pinfunction "ELE4_12") (pintype "output"))
    )
    (net (code "61") (name "Net-(TOUCH_SEL-LEFT)") (class "Default")
      (node (ref "TOUCH_SEL") (pin "L") (pinfunction "LEFT_L") (pintype "bidirectional"))
      (node (ref "U1") (pin "15") (pinfunction "ELE7_15") (pintype "output"))
    )
    (net (code "62") (name "Net-(TOUCH_SEL-RIGHT)") (class "Default")
      (node (ref "TOUCH_SEL") (pin "R") (pinfunction "RIGHT_R") (pintype "bidirectional"))
      (node (ref "U1") (pin "13") (pinfunction "ELE5_13") (pintype "output"))
    )
    (net (code "63") (name "Net-(TP139-1)") (class "Default")
      (node (ref "F1") (pin "1") (pinfunction "1_1") (pintype "bidirectional"))
      (node (ref "TP139") (pin "P$1") (pinfunction "1_P$1") (pintype "bidirectional"))
      (node (ref "USB1") (pin "1") (pinfunction "1_1") (pintype "input"))
    )
    (net (code "64") (name "Net-(U1-ELE0)") (class "Default")
      (node (ref "TOUCH_A") (pin "P$1") (pinfunction "P$1_P$1") (pintype "bidirectional"))
      (node (ref "U1") (pin "8") (pinfunction "ELE0_8") (pintype "output"))
    )
    (net (code "65") (name "Net-(U1-ELE1)") (class "Default")
      (node (ref "TOUCH_B") (pin "P$1") (pinfunction "P$1_P$1") (pintype "bidirectional"))
      (node (ref "U1") (pin "9") (pinfunction "ELE1_9") (pintype "output"))
    )
    (net (code "66") (name "Net-(U1-ELE2)") (class "Default")
      (node (ref "TOUCH_START") (pin "P$1") (pinfunction "P$1_P$1") (pintype "bidirectional"))
      (node (ref "U1") (pin "10") (pinfunction "ELE2_10") (pintype "output"))
    )
    (net (code "67") (name "Net-(U1-ELE3)") (class "Default")
      (node (ref "TOUCH_SELECT") (pin "P$1") (pinfunction "P$1_P$1") (pintype "bidirectional"))
      (node (ref "U1") (pin "11") (pinfunction "ELE3_11") (pintype "output"))
    )
    (net (code "68") (name "Net-(U1-ELE6)") (class "Default")
      (node (ref "TOUCH_SEL") (pin "UP") (pinfunction "UP_UP") (pintype "bidirectional"))
      (node (ref "U1") (pin "14") (pinfunction "ELE6_14") (pintype "output"))
    )
    (net (code "69") (name "Net-(U1-REXT)") (class "Default")
      (node (ref "R37") (pin "2") (pinfunction "2_2") (pintype "passive"))
      (node (ref "U1") (pin "7") (pinfunction "REXT_7") (pintype "input"))
    )
    (net (code "70") (name "Net-(U1-V_REG)") (class "Default")
      (node (ref "C45") (pin "1") (pinfunction "1_1") (pintype "passive"))
      (node (ref "U1") (pin "5") (pinfunction "V_REG_5") (pintype "input"))
    )
    (net (code "71") (name "PREVGH") (class "Default")
      (node (ref "C32") (pin "2") (pinfunction "2_2") (pintype "passive"))
      (node (ref "D9") (pin "C") (pinfunction "C_C") (pintype "passive"))
      (node (ref "TP104") (pin "P$1") (pinfunction "1_P$1") (pintype "bidirectional"))
      (node (ref "X1") (pin "4") (pinfunction "4_4") (pintype "passive"))
    )
    (net (code "72") (name "PREVGL") (class "Default")
      (node (ref "C36") (pin "2") (pinfunction "2_2") (pintype "passive"))
      (node (ref "D8") (pin "A") (pinfunction "A_A") (pintype "passive"))
      (node (ref "TP105") (pin "P$1") (pinfunction "1_P$1") (pintype "bidirectional"))
      (node (ref "X1") (pin "2") (pinfunction "2_2") (pintype "passive"))
    )
    (net (code "73") (name "RESE") (class "Default")
      (node (ref "Q5") (pin "2") (pinfunction "S_2") (pintype "passive"))
      (node (ref "R19") (pin "1") (pinfunction "1_1") (pintype "passive"))
      (node (ref "TP123") (pin "P$1") (pinfunction "1_P$1") (pintype "bidirectional"))
      (node (ref "X1") (pin "22") (pinfunction "22_22") (pintype "passive"))
    )
    (net (code "74") (name "SD_CD") (class "Default")
      (node (ref "R31") (pin "2") (pinfunction "2_2") (pintype "passive"))
      (node (ref "U1") (pin "19") (pinfunction "ELE11_19") (pintype "output"))
      (node (ref "X2") (pin "CD1") (pinfunction "SHIELD_CD1") (pintype "bidirectional"))
    )
    (net (code "75") (name "SD_CLK") (class "Default")
      (node (ref "IC3") (pin "13") (pinfunction "IO14_13") (pintype "bidirectional"))
      (node (ref "R25") (pin "1") (pinfunction "1_1") (pintype "passive"))
      (node (ref "X2") (pin "5") (pinfunction "SCK_5") (pintype "bidirectional"))
    )
    (net (code "76") (name "SD_CMD") (class "Default")
      (node (ref "IC3") (pin "23") (pinfunction "IO15_23") (pintype "bidirectional"))
      (node (ref "R8") (pin "1") (pinfunction "1_1") (pintype "passive"))
      (node (ref "X2") (pin "3") (pinfunction "DI_3") (pintype "bidirectional"))
    )
    (net (code "77") (name "SD_DATA0") (class "Default")
      (node (ref "D2") (pin "A") (pinfunction "A_A") (pintype "passive"))
      (node (ref "IC3") (pin "24") (pinfunction "IO2_24") (pintype "bidirectional"))
      (node (ref "R5") (pin "1") (pinfunction "1_1") (pintype "passive"))
      (node (ref "X2") (pin "7") (pinfunction "DO_7") (pintype "bidirectional"))
    )
    (net (code "78") (name "SD_DATA3") (class "Default")
      (node (ref "IC3") (pin "16") (pinfunction "IO13_16") (pintype "bidirectional"))
      (node (ref "R17") (pin "1") (pinfunction "1_1") (pintype "passive"))
      (node (ref "X2") (pin "2") (pinfunction "CS_2") (pintype "bidirectional"))
    )
    (net (code "79") (name "TEMP") (class "Default")
      (node (ref "IC4") (pin "1") (pinfunction "TEMP_1") (pintype "bidirectional"))
      (node (ref "R32") (pin "1") (pinfunction "1_1") (pintype "passive"))
      (node (ref "X4") (pin "1") (pinfunction "1_1") (pintype "passive"))
    )
    (net (code "80") (name "TSCL") (class "Default")
      (node (ref "X1") (pin "19") (pinfunction "19_19") (pintype "passive"))
    )
    (net (code "81") (name "TSDA") (class "Default")
      (node (ref "X1") (pin "18") (pinfunction "18_18") (pintype "passive"))
    )
    (net (code "82") (name "USB_DN_CON") (class "Default")
      (node (ref "IC1") (pin "5") (pinfunction "D-_5") (pintype "bidirectional"))
      (node (ref "TP137") (pin "P$1") (pinfunction "1_P$1") (pintype "bidirectional"))
      (node (ref "USB1") (pin "2") (pinfunction "2_2") (pintype "input"))
    )
    (net (code "83") (name "USB_DP_CON") (class "Default")
      (node (ref "IC1") (pin "4") (pinfunction "D+_4") (pintype "bidirectional"))
      (node (ref "TP138") (pin "P$1") (pinfunction "1_P$1") (pintype "bidirectional"))
      (node (ref "USB1") (pin "3") (pinfunction "3_3") (pintype "input"))
    )
    (net (code "84") (name "VBAT") (class "Default")
      (node (ref "F2") (pin "2") (pinfunction "2_2") (pintype "bidirectional"))
      (node (ref "R21") (pin "2") (pinfunction "2_2") (pintype "passive"))
      (node (ref "T1") (pin "3") (pinfunction "D_3") (pintype "passive"))
      (node (ref "TP110") (pin "P$1") (pinfunction "1_P$1") (pintype "bidirectional"))
    )
    (net (code "85") (name "VBAT_SENSE") (class "Default")
      (node (ref "C16") (pin "1") (pinfunction "1_1") (pintype "passive"))
      (node (ref "IC3") (pin "7") (pinfunction "IO35_7") (pintype "bidirectional"))
      (node (ref "R20") (pin "2") (pinfunction "2_2") (pintype "passive"))
      (node (ref "R21") (pin "1") (pinfunction "1_1") (pintype "passive"))
    )
    (net (code "86") (name "VCC") (class "Default")
      (node (ref "C14") (pin "1") (pinfunction "1_1") (pintype "passive"))
      (node (ref "C15") (pin "1") (pinfunction "1_1") (pintype "passive"))
      (node (ref "C18") (pin "1") (pinfunction "1_1") (pintype "passive"))
      (node (ref "D3") (pin "C") (pinfunction "C_C") (pintype "passive"))
      (node (ref "IC2") (pin "3") (pinfunction "IN_3") (pintype "input"))
      (node (ref "R2") (pin "2") (pinfunction "2_2") (pintype "passive"))
      (node (ref "R9") (pin "2") (pinfunction "2_2") (pintype "passive"))
      (node (ref "T1") (pin "2") (pinfunction "S_2") (pintype "passive"))
      (node (ref "T2") (pin "2") (pinfunction "S_2") (pintype "passive"))
      (node (ref "TP129") (pin "P$1") (pinfunction "1_P$1") (pintype "bidirectional"))
    )
    (net (code "87") (name "VCOM") (class "Default")
      (node (ref "C38") (pin "2") (pinfunction "2_2") (pintype "passive"))
      (node (ref "X1") (pin "1") (pinfunction "1_1") (pintype "passive"))
    )
    (net (code "88") (name "VDD") (class "Default")
      (node (ref "C8") (pin "1") (pinfunction "1_1") (pintype "passive"))
      (node (ref "IC1") (pin "6") (pinfunction "VDD_6") (pintype "power_in"))
      (node (ref "R12") (pin "2") (pinfunction "2_2") (pintype "passive"))
      (node (ref "R13") (pin "1") (pinfunction "1_1") (pintype "passive"))
      (node (ref "R14") (pin "2") (pinfunction "2_2") (pintype "passive"))
      (node (ref "R3") (pin "2") (pinfunction "2_2") (pintype "passive"))
    )
    (net (code "89") (name "VGH") (class "Default")
      (node (ref "C21") (pin "2") (pinfunction "2_2") (pintype "passive"))
      (node (ref "X1") (pin "20") (pinfunction "20_20") (pintype "passive"))
    )
    (net (code "90") (name "VGL") (class "Default")
      (node (ref "C19") (pin "2") (pinfunction "2_2") (pintype "passive"))
      (node (ref "X1") (pin "21") (pinfunction "21_21") (pintype "passive"))
    )
    (net (code "91") (name "VIBRATOR") (class "Default")
      (node (ref "R11") (pin "2") (pinfunction "2_2") (pintype "passive"))
      (node (ref "U1") (pin "16") (pinfunction "ELE8_16") (pintype "output"))
    )
    (net (code "92") (name "VPP") (class "Default")
      (node (ref "X1") (pin "6") (pinfunction "6_6") (pintype "passive"))
    )
    (net (code "93") (name "VSH") (class "Default")
      (node (ref "C33") (pin "2") (pinfunction "2_2") (pintype "passive"))
      (node (ref "X1") (pin "5") (pinfunction "5_5") (pintype "passive"))
    )
    (net (code "94") (name "VSL") (class "Default")
      (node (ref "C35") (pin "2") (pinfunction "2_2") (pintype "passive"))
      (node (ref "X1") (pin "3") (pinfunction "3_3") (pintype "passive"))
    )
    (net (code "95") (name "VUSB_SENSE") (class "Default")
      (node (ref "C10") (pin "1") (pinfunction "1_1") (pintype "passive"))
      (node (ref "IC3") (pin "6") (pinfunction "IO34_6") (pintype "bidirectional"))
      (node (ref "R6") (pin "2") (pinfunction "2_2") (pintype "passive"))
      (node (ref "R7") (pin "1") (pinfunction "1_1") (pintype "passive"))
    )
    (net (code "96") (name "WS2812_DATA") (class "Default")
      (node (ref "D105") (pin "4") (pinfunction "DIN_4") (pintype "input"))
      (node (ref "IC3") (pin "8") (pinfunction "IO32_8") (pintype "bidirectional"))
      (node (ref "TP136") (pin "P$1") (pinfunction "1_P$1") (pintype "bidirectional"))
    )
    (net (code "97") (name "WS2812_DATA_OUT") (class "Default")
      (node (ref "D100") (pin "2") (pinfunction "DOUT_2") (pintype "output"))
      (node (ref "X3") (pin "8") (pinfunction "5_8") (pintype "passive"))
    )
    (net (code "98") (name "WS2812_POWER") (class "Default")
      (node (ref "C1") (pin "2") (pinfunction "2_2") (pintype "passive"))
      (node (ref "C13") (pin "1") (pinfunction "1_1") (pintype "passive"))
      (node (ref "C2") (pin "2") (pinfunction "2_2") (pintype "passive"))
      (node (ref "C3") (pin "2") (pinfunction "2_2") (pintype "passive"))
      (node (ref "C4") (pin "2") (pinfunction "2_2") (pintype "passive"))
      (node (ref "C5") (pin "2") (pinfunction "2_2") (pintype "passive"))
      (node (ref "C6") (pin "2") (pinfunction "2_2") (pintype "passive"))
      (node (ref "D100") (pin "1") (pinfunction "VDD_1") (pintype "power_in"))
      (node (ref "D101") (pin "1") (pinfunction "VDD_1") (pintype "power_in"))
      (node (ref "D102") (pin "1") (pinfunction "VDD_1") (pintype "power_in"))
      (node (ref "D103") (pin "1") (pinfunction "VDD_1") (pintype "power_in"))
      (node (ref "D104") (pin "1") (pinfunction "VDD_1") (pintype "power_in"))
      (node (ref "D105") (pin "1") (pinfunction "VDD_1") (pintype "power_in"))
      (node (ref "T2") (pin "3") (pinfunction "D_3") (pintype "passive"))
      (node (ref "TP117") (pin "P$1") (pinfunction "1_P$1") (pintype "bidirectional"))
      (node (ref "X3") (pin "2") (pinfunction "11_2") (pintype "passive"))
    )
    (net (code "99") (name "WS2812_POWER_EN") (class "Default")
      (node (ref "R10") (pin "1") (pinfunction "1_1") (pintype "passive"))
      (node (ref "R27") (pin "1") (pinfunction "1_1") (pintype "passive"))
      (node (ref "U1") (pin "18") (pinfunction "ELE10_18") (pintype "output"))
    )
    (net (code "100") (name "unconnected-(IC1-CTS-Pad23)") (class "Default")
      (node (ref "IC1") (pin "23") (pinfunction "CTS_23") (pintype "input"))
    )
    (net (code "101") (name "unconnected-(IC1-DCD-Pad1)") (class "Default")
      (node (ref "IC1") (pin "1") (pinfunction "DCD_1") (pintype "input"))
    )
    (net (code "102") (name "unconnected-(IC1-DSR-Pad27)") (class "Default")
      (node (ref "IC1") (pin "27") (pinfunction "DSR_27") (pintype "input"))
    )
    (net (code "103") (name "unconnected-(IC1-RI-Pad2)") (class "Default")
      (node (ref "IC1") (pin "2") (pinfunction "RI_2") (pintype "input"))
    )
    (net (code "104") (name "unconnected-(IC1-SUSPEND-Pad12)") (class "Default")
      (node (ref "IC1") (pin "12") (pinfunction "SUSPEND_12") (pintype "output"))
    )
    (net (code "105") (name "unconnected-(IC1-~{SUSPEND}-Pad11)") (class "Default")
      (node (ref "IC1") (pin "11") (pinfunction "~{SUSPEND}_11") (pintype "output"))
    )
    (net (code "106") (name "unconnected-(IC3-IO20-Pad32)") (class "Default")
      (node (ref "IC3") (pin "32") (pinfunction "IO20_32") (pintype "bidirectional"))
    )
    (net (code "107") (name "unconnected-(IC4-STDBY-Pad6)") (class "Default")
      (node (ref "IC4") (pin "6") (pinfunction "STDBY_6") (pintype "bidirectional"))
    )
    (net (code "108") (name "unconnected-(USB1-Pad4)") (class "Default")
      (node (ref "USB1") (pin "4") (pinfunction "4_4") (pintype "input"))
    )
    (net (code "109") (name "unconnected-(X1-Pad24)") (class "Default")
      (node (ref "X1") (pin "24") (pinfunction "24_24") (pintype "passive"))
    )
    (net (code "110") (name "unconnected-(X2-NC-Pad1)") (class "Default")
      (node (ref "X2") (pin "1") (pinfunction "NC_1") (pintype "bidirectional"))
    )
    (net (code "111") (name "unconnected-(X2-RSV-Pad8)") (class "Default")
      (node (ref "X2") (pin "8") (pinfunction "RSV_8") (pintype "bidirectional"))
    )
  )
)
